# homeboard13.net
KiCad netlist of a schematic drawn in EAGLE
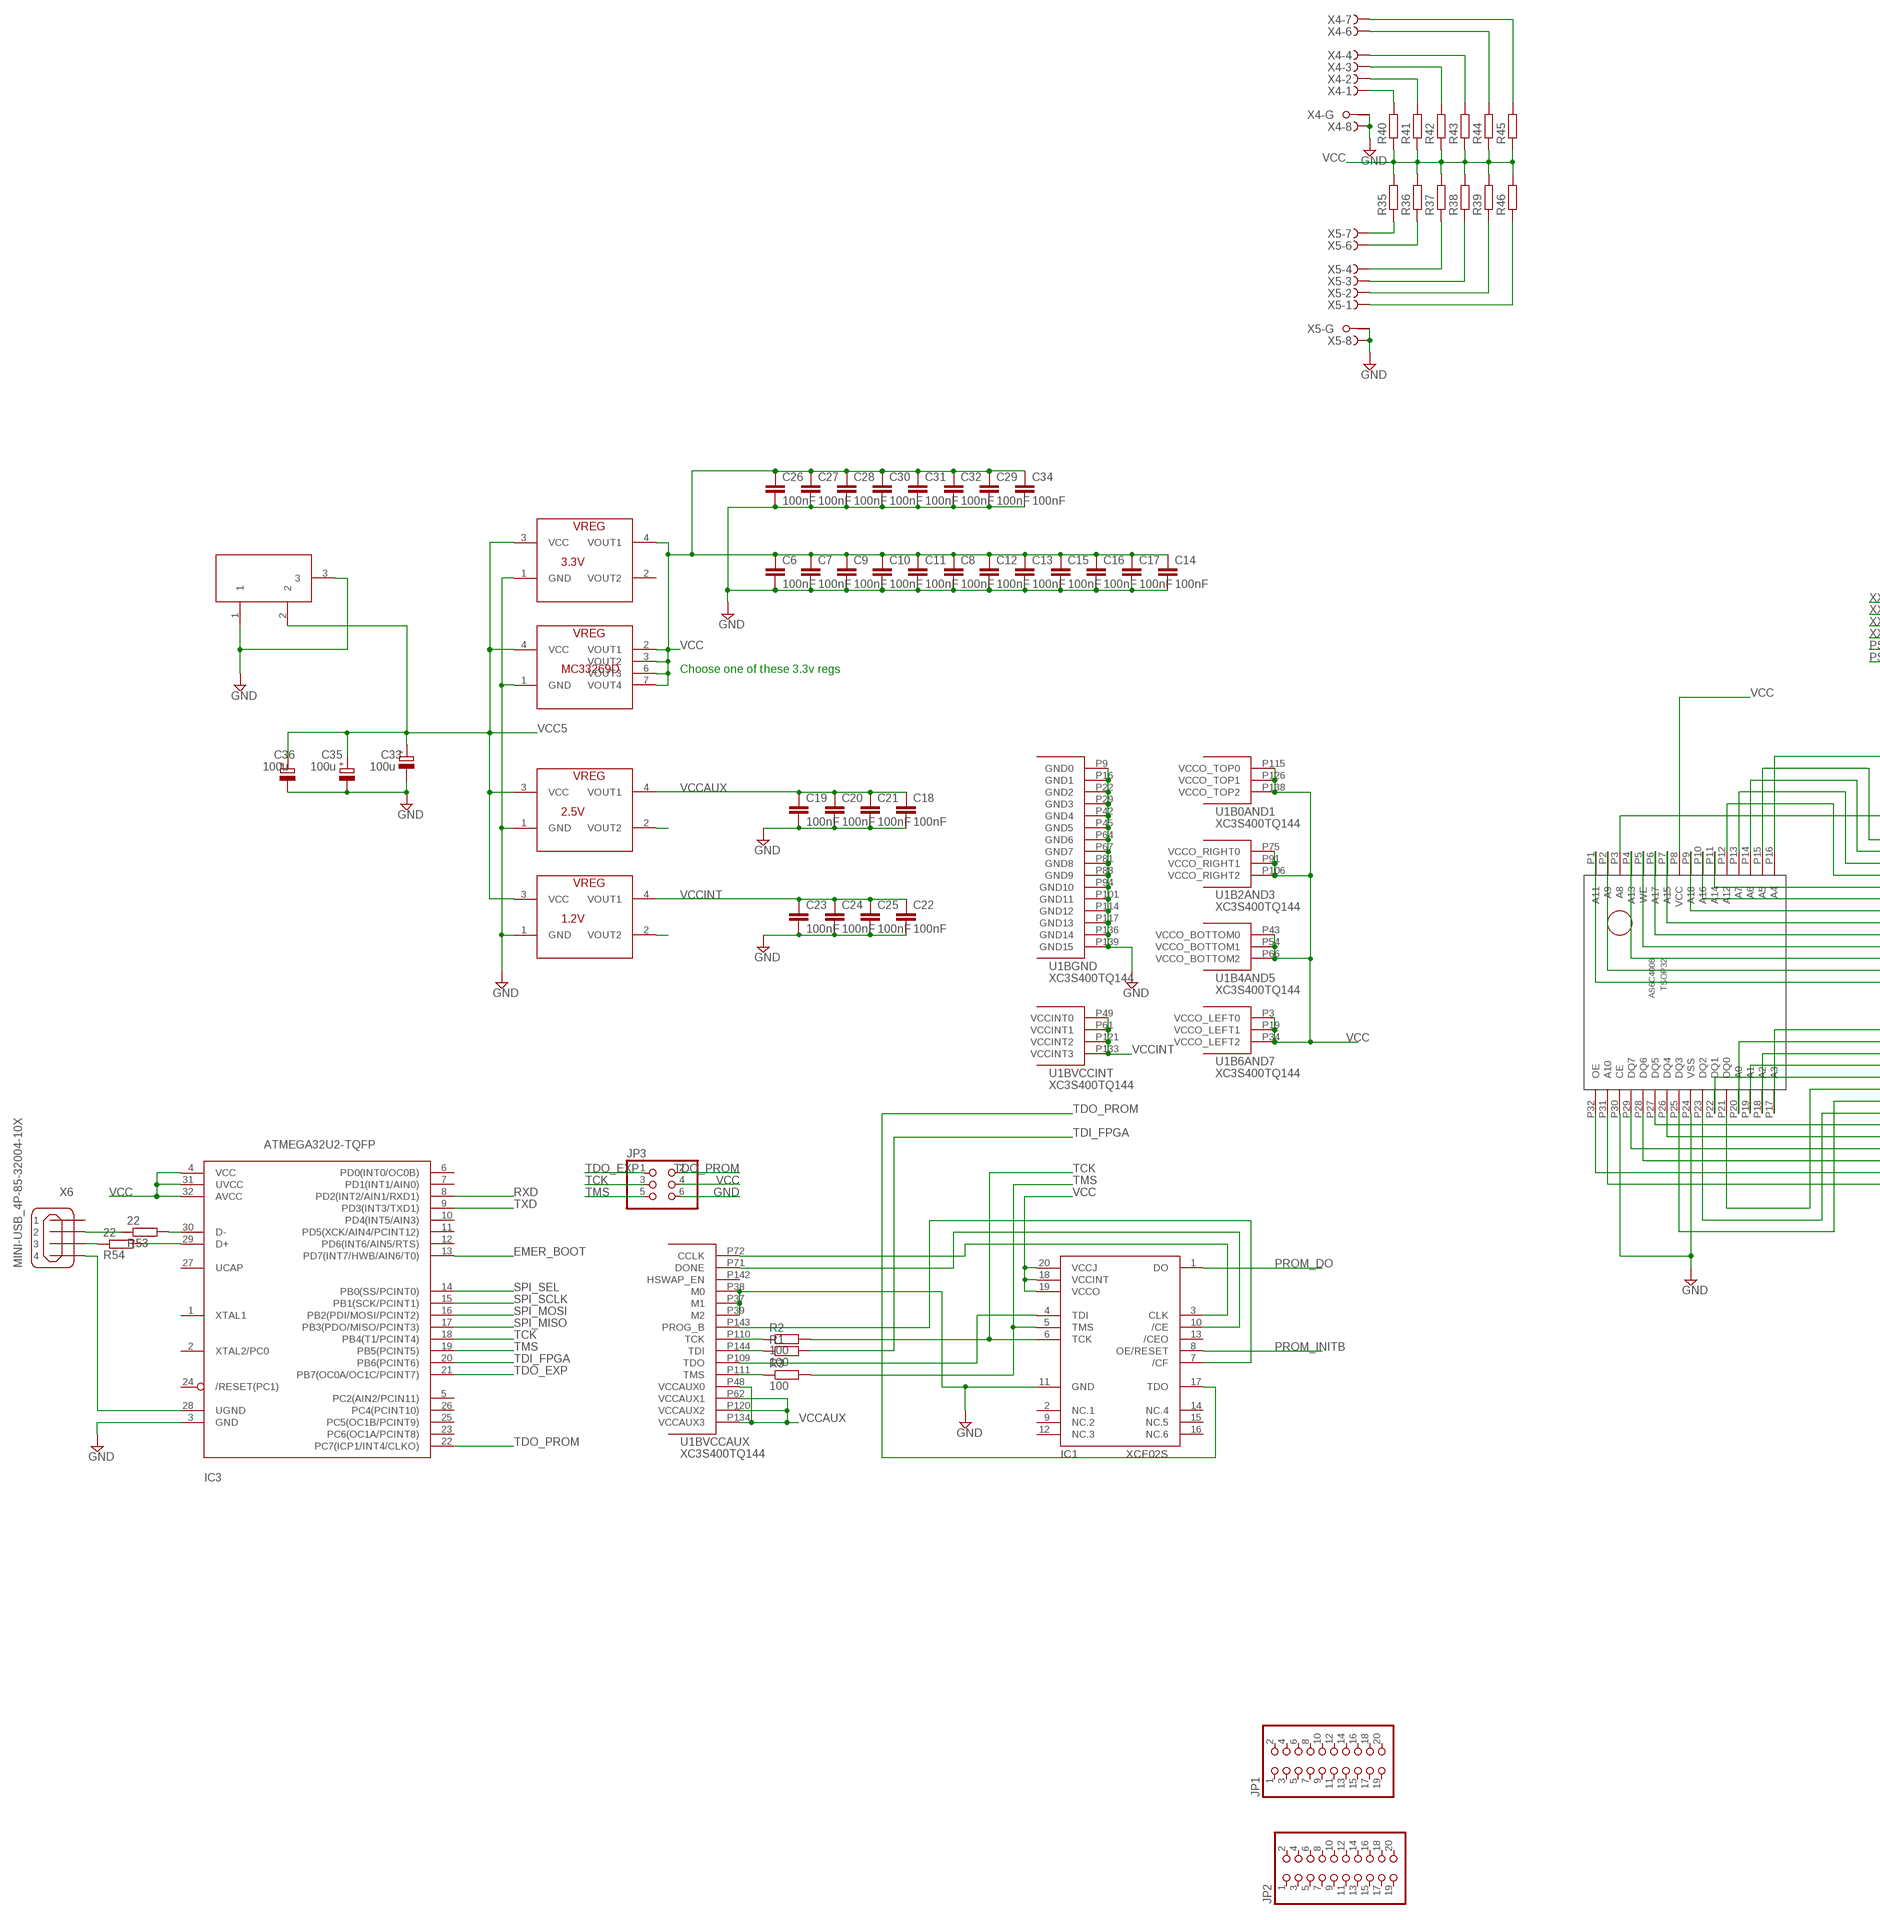
[diagram p0: schematic, sheet 1, part 1 of 3]
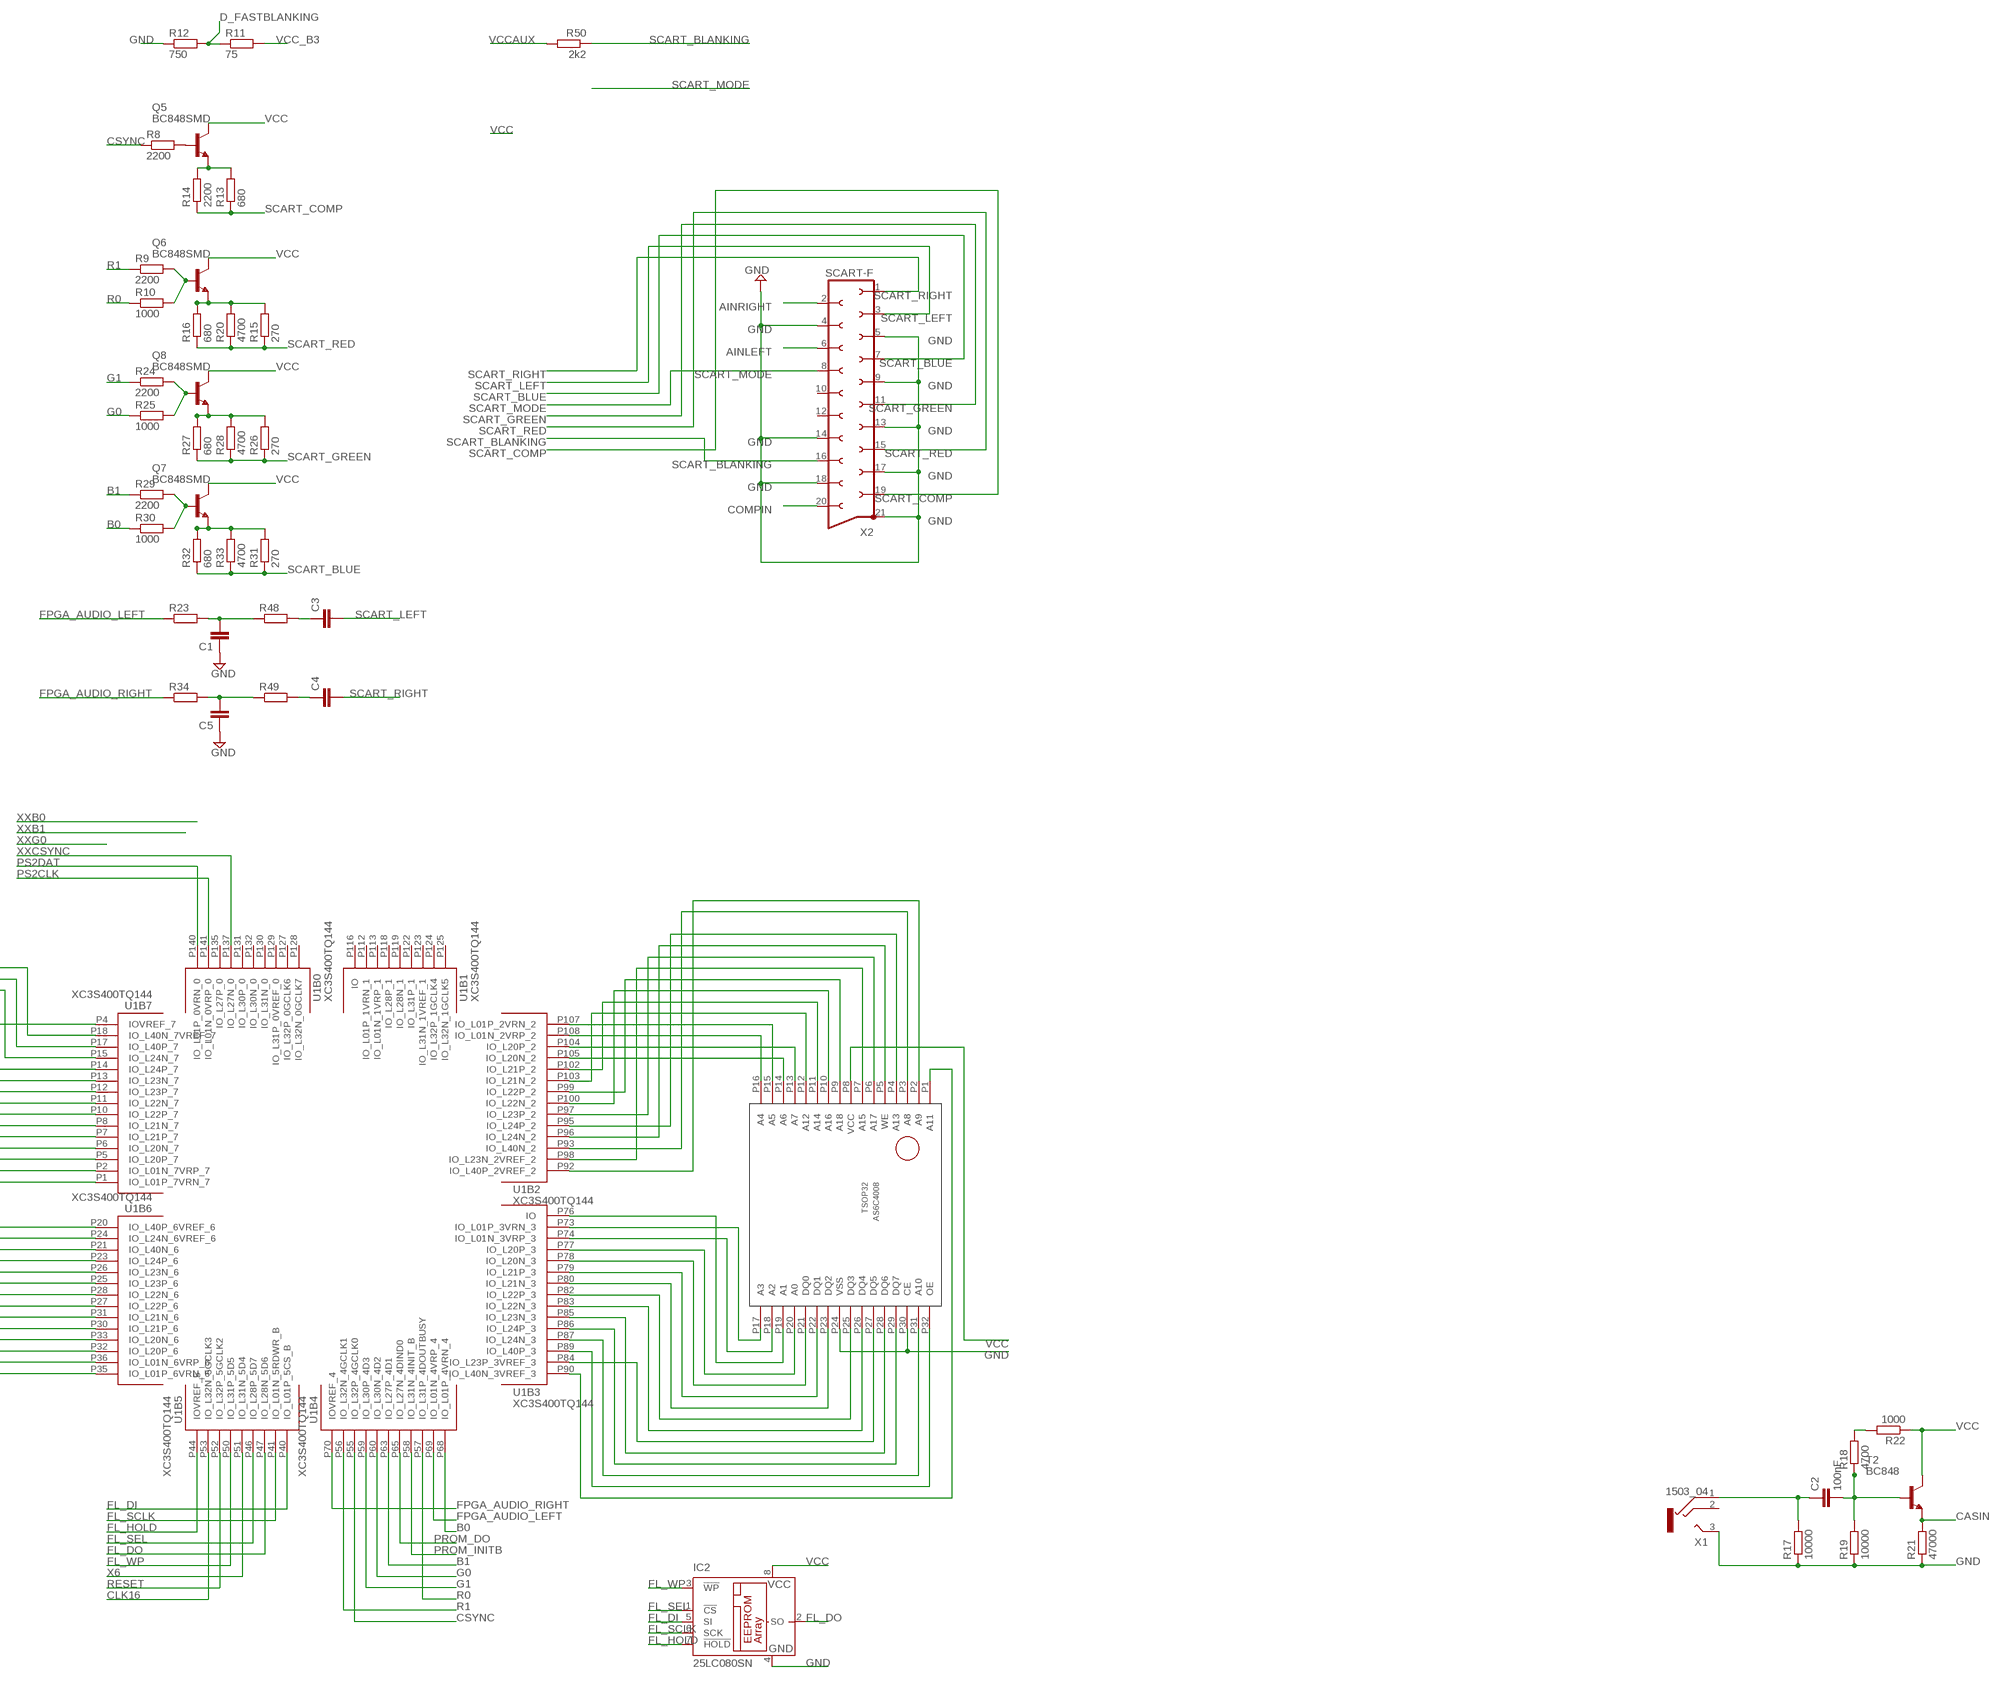
[diagram p1: schematic, sheet 1, part 2 of 3]
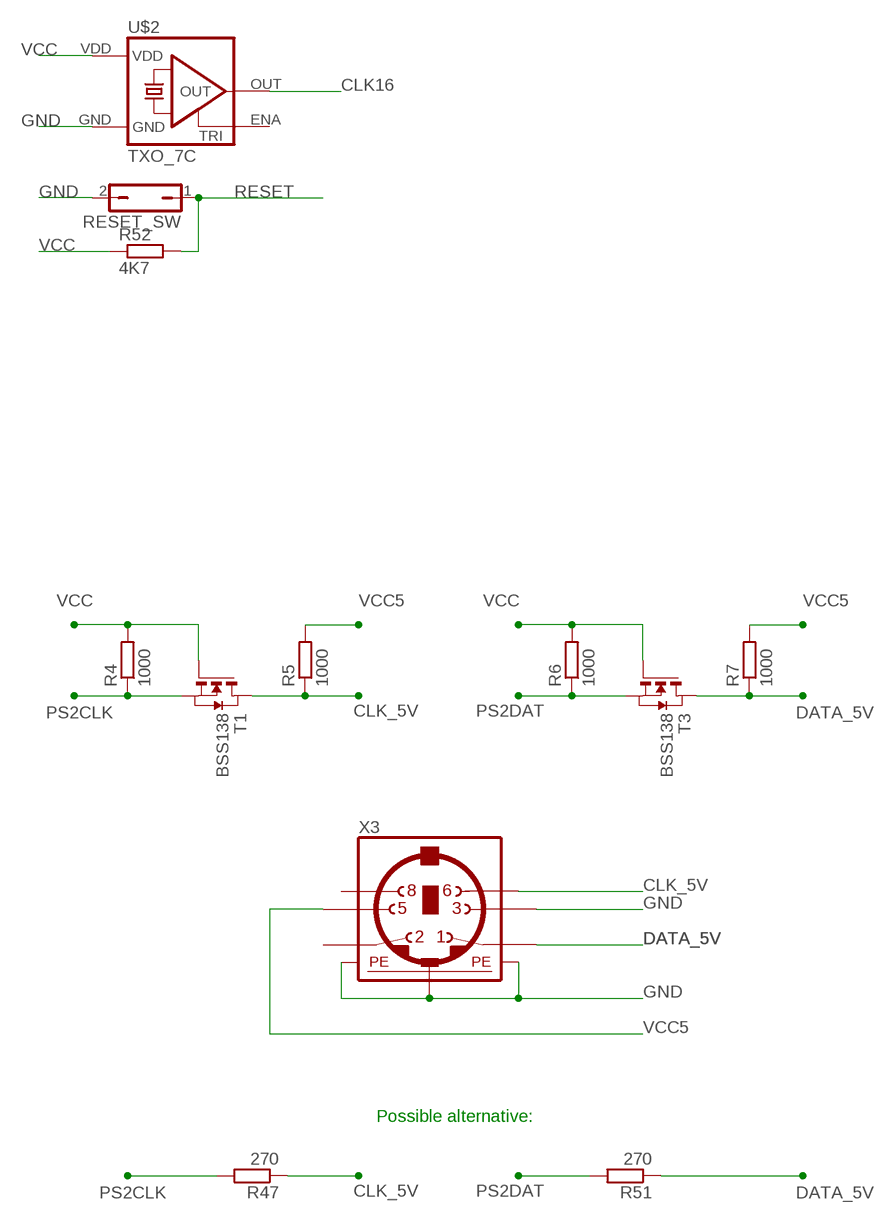
[diagram p2: schematic, sheet 1, part 3 of 3]

(export (version "E")
  (design (tool "Eeschema 10.0.6"))
  (components
    (comp (ref "C1")
      (value "C-EUC0603")
      (footprint "eagle-import:C0603")
      (libsource (lib "eagle-import") (part "resistor_C-EUC0603"))
    )
    (comp (ref "C2")
      (value "100nF")
      (footprint "eagle-import:C0603")
      (libsource (lib "eagle-import") (part "resistor_C-EUC0603"))
    )
    (comp (ref "C3")
      (value "C-EUC0603")
      (footprint "eagle-import:C0603")
      (libsource (lib "eagle-import") (part "resistor_C-EUC0603"))
    )
    (comp (ref "C4")
      (value "C-EUC0603")
      (footprint "eagle-import:C0603")
      (libsource (lib "eagle-import") (part "resistor_C-EUC0603"))
    )
    (comp (ref "C5")
      (value "C-EUC0603")
      (footprint "eagle-import:C0603")
      (libsource (lib "eagle-import") (part "resistor_C-EUC0603"))
    )
    (comp (ref "C6")
      (value "100nF")
      (footprint "eagle-import:C0603")
      (libsource (lib "eagle-import") (part "C-EUC0603"))
    )
    (comp (ref "C7")
      (value "100nF")
      (footprint "eagle-import:C0603")
      (libsource (lib "eagle-import") (part "C-EUC0603"))
    )
    (comp (ref "C8")
      (value "100nF")
      (footprint "eagle-import:C0603")
      (libsource (lib "eagle-import") (part "C-EUC0603"))
    )
    (comp (ref "C9")
      (value "100nF")
      (footprint "eagle-import:C0603")
      (libsource (lib "eagle-import") (part "C-EUC0603"))
    )
    (comp (ref "C10")
      (value "100nF")
      (footprint "eagle-import:C0603")
      (libsource (lib "eagle-import") (part "C-EUC0603"))
    )
    (comp (ref "C11")
      (value "100nF")
      (footprint "eagle-import:C0603")
      (libsource (lib "eagle-import") (part "C-EUC0603"))
    )
    (comp (ref "C12")
      (value "100nF")
      (footprint "eagle-import:C0603")
      (libsource (lib "eagle-import") (part "C-EUC0603"))
    )
    (comp (ref "C13")
      (value "100nF")
      (footprint "eagle-import:C0603")
      (libsource (lib "eagle-import") (part "C-EUC0603"))
    )
    (comp (ref "C14")
      (value "100nF")
      (footprint "eagle-import:C0603")
      (libsource (lib "eagle-import") (part "C-EUC0603"))
    )
    (comp (ref "C15")
      (value "100nF")
      (footprint "eagle-import:C0603")
      (libsource (lib "eagle-import") (part "C-EUC0603"))
    )
    (comp (ref "C16")
      (value "100nF")
      (footprint "eagle-import:C0603")
      (libsource (lib "eagle-import") (part "C-EUC0603"))
    )
    (comp (ref "C17")
      (value "100nF")
      (footprint "eagle-import:C0603")
      (libsource (lib "eagle-import") (part "C-EUC0603"))
    )
    (comp (ref "C18")
      (value "100nF")
      (footprint "eagle-import:C0603")
      (libsource (lib "eagle-import") (part "C-EUC0603"))
    )
    (comp (ref "C19")
      (value "100nF")
      (footprint "eagle-import:C0603")
      (libsource (lib "eagle-import") (part "C-EUC0603"))
    )
    (comp (ref "C20")
      (value "100nF")
      (footprint "eagle-import:C0603")
      (libsource (lib "eagle-import") (part "C-EUC0603"))
    )
    (comp (ref "C21")
      (value "100nF")
      (footprint "eagle-import:C0603")
      (libsource (lib "eagle-import") (part "C-EUC0603"))
    )
    (comp (ref "C22")
      (value "100nF")
      (footprint "eagle-import:C0603")
      (libsource (lib "eagle-import") (part "C-EUC0603"))
    )
    (comp (ref "C23")
      (value "100nF")
      (footprint "eagle-import:C0603")
      (libsource (lib "eagle-import") (part "C-EUC0603"))
    )
    (comp (ref "C24")
      (value "100nF")
      (footprint "eagle-import:C0603")
      (libsource (lib "eagle-import") (part "C-EUC0603"))
    )
    (comp (ref "C25")
      (value "100nF")
      (footprint "eagle-import:C0603")
      (libsource (lib "eagle-import") (part "C-EUC0603"))
    )
    (comp (ref "C26")
      (value "100nF")
      (footprint "eagle-import:C0603")
      (libsource (lib "eagle-import") (part "C-EUC0603"))
    )
    (comp (ref "C27")
      (value "100nF")
      (footprint "eagle-import:C0603")
      (libsource (lib "eagle-import") (part "C-EUC0603"))
    )
    (comp (ref "C28")
      (value "100nF")
      (footprint "eagle-import:C0603")
      (libsource (lib "eagle-import") (part "C-EUC0603"))
    )
    (comp (ref "C29")
      (value "100nF")
      (footprint "eagle-import:C0603")
      (libsource (lib "eagle-import") (part "C-EUC0603"))
    )
    (comp (ref "C30")
      (value "100nF")
      (footprint "eagle-import:C0603")
      (libsource (lib "eagle-import") (part "C-EUC0603"))
    )
    (comp (ref "C31")
      (value "100nF")
      (footprint "eagle-import:C0603")
      (libsource (lib "eagle-import") (part "C-EUC0603"))
    )
    (comp (ref "C32")
      (value "100nF")
      (footprint "eagle-import:C0603")
      (libsource (lib "eagle-import") (part "C-EUC0603"))
    )
    (comp (ref "C33")
      (value "100u")
      (footprint "eagle-import:PANASONIC_D")
      (libsource (lib "eagle-import") (part "CPOL-EUD"))
    )
    (comp (ref "C34")
      (value "100nF")
      (footprint "eagle-import:C0603")
      (libsource (lib "eagle-import") (part "C-EUC0603"))
    )
    (comp (ref "C35")
      (value "100u")
      (footprint "eagle-import:PANASONIC_D")
      (libsource (lib "eagle-import") (part "CPOL-EUD"))
    )
    (comp (ref "C36")
      (value "100u")
      (footprint "eagle-import:PANASONIC_D")
      (libsource (lib "eagle-import") (part "CPOL-EUD"))
    )
    (comp (ref "IC1")
      (value "XCF02S")
      (footprint "eagle-import:VO20")
      (libsource (lib "eagle-import") (part "XCF02S"))
    )
    (comp (ref "IC2")
      (value "25LC080SN")
      (footprint "eagle-import:SO-08")
      (fields (field (name "MF") "MICROCHIP") (field (name "MPN") "25LC080/SN"))
      (libsource (lib "eagle-import") (part "25SNLC080"))
    )
    (comp (ref "IC3")
      (value "ATMEGA32U2-TQFP")
      (footprint "eagle-import:TQFP32-08")
      (libsource (lib "eagle-import") (part "ATMEGA32U2-TQFP"))
    )
    (comp (ref "JP1")
      (value "PINHD-2X10")
      (footprint "eagle-import:2X10")
      (libsource (lib "eagle-import") (part "PINHD-2X10"))
    )
    (comp (ref "JP2")
      (value "PINHD-2X10")
      (footprint "eagle-import:2X10")
      (libsource (lib "eagle-import") (part "PINHD-2X10"))
    )
    (comp (ref "JP3")
      (value "PINHD-2X3")
      (footprint "eagle-import:2X03")
      (libsource (lib "eagle-import") (part "PINHD-2X3"))
    )
    (comp (ref "Q5")
      (value "BC848SMD")
      (footprint "eagle-import:SOT23")
      (libsource (lib "eagle-import") (part "BC848SMD"))
    )
    (comp (ref "Q6")
      (value "BC848SMD")
      (footprint "eagle-import:SOT23")
      (libsource (lib "eagle-import") (part "BC848SMD"))
    )
    (comp (ref "Q7")
      (value "BC848SMD")
      (footprint "eagle-import:SOT23")
      (libsource (lib "eagle-import") (part "BC848SMD"))
    )
    (comp (ref "Q8")
      (value "BC848SMD")
      (footprint "eagle-import:SOT23")
      (libsource (lib "eagle-import") (part "BC848SMD"))
    )
    (comp (ref "R1")
      (value "100")
      (footprint "eagle-import:R0805")
      (libsource (lib "eagle-import") (part "R-EU_R0805"))
    )
    (comp (ref "R2")
      (value "100")
      (footprint "eagle-import:R0805")
      (libsource (lib "eagle-import") (part "R-EU_R0805"))
    )
    (comp (ref "R3")
      (value "100")
      (footprint "eagle-import:R0805")
      (libsource (lib "eagle-import") (part "R-EU_R0805"))
    )
    (comp (ref "R4")
      (value "1000")
      (footprint "eagle-import:R0805")
      (libsource (lib "eagle-import") (part "R-EU_R0805"))
    )
    (comp (ref "R5")
      (value "1000")
      (footprint "eagle-import:R0805")
      (libsource (lib "eagle-import") (part "R-EU_R0805"))
    )
    (comp (ref "R6")
      (value "1000")
      (footprint "eagle-import:R0805")
      (libsource (lib "eagle-import") (part "R-EU_R0805"))
    )
    (comp (ref "R7")
      (value "1000")
      (footprint "eagle-import:R0805")
      (libsource (lib "eagle-import") (part "R-EU_R0805"))
    )
    (comp (ref "R8")
      (value "2200")
      (footprint "eagle-import:R0805")
      (libsource (lib "eagle-import") (part "R-EU_R0805"))
    )
    (comp (ref "R9")
      (value "2200")
      (footprint "eagle-import:R0805")
      (libsource (lib "eagle-import") (part "R-EU_R0805"))
    )
    (comp (ref "R10")
      (value "1000")
      (footprint "eagle-import:R0805")
      (libsource (lib "eagle-import") (part "R-EU_R0805"))
    )
    (comp (ref "R11")
      (value "75")
      (footprint "eagle-import:R0805")
      (libsource (lib "eagle-import") (part "R-EU_R0805"))
    )
    (comp (ref "R12")
      (value "750")
      (footprint "eagle-import:R0805")
      (libsource (lib "eagle-import") (part "R-EU_R0805"))
    )
    (comp (ref "R13")
      (value "680")
      (footprint "eagle-import:R0805")
      (libsource (lib "eagle-import") (part "R-EU_R0805"))
    )
    (comp (ref "R14")
      (value "2200")
      (footprint "eagle-import:R0805")
      (libsource (lib "eagle-import") (part "R-EU_R0805"))
    )
    (comp (ref "R15")
      (value "270")
      (footprint "eagle-import:R0805")
      (libsource (lib "eagle-import") (part "R-EU_R0805"))
    )
    (comp (ref "R16")
      (value "680")
      (footprint "eagle-import:R0805")
      (libsource (lib "eagle-import") (part "R-EU_R0805"))
    )
    (comp (ref "R17")
      (value "10000")
      (footprint "eagle-import:R0805")
      (libsource (lib "eagle-import") (part "R-EU_R0805"))
    )
    (comp (ref "R18")
      (value "4700")
      (footprint "eagle-import:R0805")
      (libsource (lib "eagle-import") (part "R-EU_R0805"))
    )
    (comp (ref "R19")
      (value "10000")
      (footprint "eagle-import:R0805")
      (libsource (lib "eagle-import") (part "R-EU_R0805"))
    )
    (comp (ref "R20")
      (value "4700")
      (footprint "eagle-import:R0805")
      (libsource (lib "eagle-import") (part "R-EU_R0805"))
    )
    (comp (ref "R21")
      (value "47000")
      (footprint "eagle-import:R0805")
      (libsource (lib "eagle-import") (part "R-EU_R0805"))
    )
    (comp (ref "R22")
      (value "1000")
      (footprint "eagle-import:R0805")
      (libsource (lib "eagle-import") (part "R-EU_R0805"))
    )
    (comp (ref "R23")
      (value "R-EU_M0805")
      (footprint "eagle-import:M0805")
      (libsource (lib "eagle-import") (part "resistor_R-EU_M0805"))
    )
    (comp (ref "R24")
      (value "2200")
      (footprint "eagle-import:R0805")
      (libsource (lib "eagle-import") (part "R-EU_R0805"))
    )
    (comp (ref "R25")
      (value "1000")
      (footprint "eagle-import:R0805")
      (libsource (lib "eagle-import") (part "R-EU_R0805"))
    )
    (comp (ref "R26")
      (value "270")
      (footprint "eagle-import:R0805")
      (libsource (lib "eagle-import") (part "R-EU_R0805"))
    )
    (comp (ref "R27")
      (value "680")
      (footprint "eagle-import:R0805")
      (libsource (lib "eagle-import") (part "R-EU_R0805"))
    )
    (comp (ref "R28")
      (value "4700")
      (footprint "eagle-import:R0805")
      (libsource (lib "eagle-import") (part "R-EU_R0805"))
    )
    (comp (ref "R29")
      (value "2200")
      (footprint "eagle-import:R0805")
      (libsource (lib "eagle-import") (part "R-EU_R0805"))
    )
    (comp (ref "R30")
      (value "1000")
      (footprint "eagle-import:R0805")
      (libsource (lib "eagle-import") (part "R-EU_R0805"))
    )
    (comp (ref "R31")
      (value "270")
      (footprint "eagle-import:R0805")
      (libsource (lib "eagle-import") (part "R-EU_R0805"))
    )
    (comp (ref "R32")
      (value "680")
      (footprint "eagle-import:R0805")
      (libsource (lib "eagle-import") (part "R-EU_R0805"))
    )
    (comp (ref "R33")
      (value "4700")
      (footprint "eagle-import:R0805")
      (libsource (lib "eagle-import") (part "R-EU_R0805"))
    )
    (comp (ref "R34")
      (value "R-EU_M0805")
      (footprint "eagle-import:M0805")
      (libsource (lib "eagle-import") (part "resistor_R-EU_M0805"))
    )
    (comp (ref "R35")
      (value "R-EU_M0805")
      (footprint "eagle-import:M0805")
      (libsource (lib "eagle-import") (part "resistor_R-EU_M0805"))
    )
    (comp (ref "R36")
      (value "R-EU_M0805")
      (footprint "eagle-import:M0805")
      (libsource (lib "eagle-import") (part "resistor_R-EU_M0805"))
    )
    (comp (ref "R37")
      (value "R-EU_M0805")
      (footprint "eagle-import:M0805")
      (libsource (lib "eagle-import") (part "resistor_R-EU_M0805"))
    )
    (comp (ref "R38")
      (value "R-EU_M0805")
      (footprint "eagle-import:M0805")
      (libsource (lib "eagle-import") (part "resistor_R-EU_M0805"))
    )
    (comp (ref "R39")
      (value "R-EU_M0805")
      (footprint "eagle-import:M0805")
      (libsource (lib "eagle-import") (part "resistor_R-EU_M0805"))
    )
    (comp (ref "R40")
      (value "R-EU_M0805")
      (footprint "eagle-import:M0805")
      (libsource (lib "eagle-import") (part "resistor_R-EU_M0805"))
    )
    (comp (ref "R41")
      (value "R-EU_M0805")
      (footprint "eagle-import:M0805")
      (libsource (lib "eagle-import") (part "resistor_R-EU_M0805"))
    )
    (comp (ref "R42")
      (value "R-EU_M0805")
      (footprint "eagle-import:M0805")
      (libsource (lib "eagle-import") (part "resistor_R-EU_M0805"))
    )
    (comp (ref "R43")
      (value "R-EU_M0805")
      (footprint "eagle-import:M0805")
      (libsource (lib "eagle-import") (part "resistor_R-EU_M0805"))
    )
    (comp (ref "R44")
      (value "R-EU_M0805")
      (footprint "eagle-import:M0805")
      (libsource (lib "eagle-import") (part "resistor_R-EU_M0805"))
    )
    (comp (ref "R45")
      (value "R-EU_M0805")
      (footprint "eagle-import:M0805")
      (libsource (lib "eagle-import") (part "resistor_R-EU_M0805"))
    )
    (comp (ref "R46")
      (value "R-EU_M0805")
      (footprint "eagle-import:M0805")
      (libsource (lib "eagle-import") (part "resistor_R-EU_M0805"))
    )
    (comp (ref "R47")
      (value "270")
      (footprint "eagle-import:R0805")
      (libsource (lib "eagle-import") (part "R-EU_R0805"))
    )
    (comp (ref "R48")
      (value "R-EU_M0805")
      (footprint "eagle-import:M0805")
      (libsource (lib "eagle-import") (part "resistor_R-EU_M0805"))
    )
    (comp (ref "R49")
      (value "R-EU_M0805")
      (footprint "eagle-import:M0805")
      (libsource (lib "eagle-import") (part "resistor_R-EU_M0805"))
    )
    (comp (ref "R50")
      (value "2k2")
      (footprint "eagle-import:M0805")
      (libsource (lib "eagle-import") (part "resistor_R-EU_M0805"))
    )
    (comp (ref "R51")
      (value "270")
      (footprint "eagle-import:R0805")
      (libsource (lib "eagle-import") (part "R-EU_R0805"))
    )
    (comp (ref "R52")
      (value "4K7")
      (footprint "eagle-import:M0805")
      (libsource (lib "eagle-import") (part "resistor_R-EU_M0805"))
    )
    (comp (ref "R53")
      (value "22")
      (footprint "eagle-import:R0805")
      (libsource (lib "eagle-import") (part "R-EU_R0805"))
    )
    (comp (ref "R54")
      (value "22")
      (footprint "eagle-import:R0805")
      (libsource (lib "eagle-import") (part "R-EU_R0805"))
    )
    (comp (ref "REG1.2")
      (value "1.2V")
      (footprint "eagle-import:SOT223")
      (libsource (lib "eagle-import") (part "NX1117"))
    )
    (comp (ref "REG2.5")
      (value "2.5V")
      (footprint "eagle-import:SOT223")
      (libsource (lib "eagle-import") (part "NX1117"))
    )
    (comp (ref "RESET_SW")
      (value "JP1Q")
      (footprint "eagle-import:JP1")
      (libsource (lib "eagle-import") (part "JP1Q"))
    )
    (comp (ref "T1")
      (value "BSS138")
      (footprint "eagle-import:SOT-23")
      (libsource (lib "eagle-import") (part "NMOSSOT23"))
    )
    (comp (ref "T2")
      (value "BC848")
      (footprint "eagle-import:SOT23")
      (libsource (lib "eagle-import") (part "BC848"))
    )
    (comp (ref "T3")
      (value "BSS138")
      (footprint "eagle-import:SOT-23")
      (libsource (lib "eagle-import") (part "NMOSSOT23"))
    )
    (comp (ref "U$1")
      (value "AS6C4008")
      (footprint "eagle-import:TSOP32")
      (libsource (lib "eagle-import") (part "AS6C4008"))
    )
    (comp (ref "U$2")
      (value "TXO_7C")
      (footprint "eagle-import:OSC_7C")
      (libsource (lib "eagle-import") (part "TXO_7C"))
    )
    (comp (ref "U$4")
      (value "3.3V")
      (footprint "eagle-import:SOT223")
      (libsource (lib "eagle-import") (part "NX1117"))
    )
    (comp (ref "U$5")
      (value "MC33269D")
      (footprint "eagle-import:SO8")
      (libsource (lib "eagle-import") (part "MC33269D"))
    )
    (comp (ref "U$6")
      (value "AS6C4008")
      (footprint "eagle-import:TSOP32")
      (libsource (lib "eagle-import") (part "AS6C4008"))
    )
    (comp (ref "U1")
      (value "XC3S400TQ144")
      (footprint "eagle-import:TQ144")
      (libsource (lib "eagle-import") (part "XC3S400TQ144"))
    )
    (comp (ref "X1")
      (value "1503_04")
      (footprint "eagle-import:1503_04")
      (libsource (lib "eagle-import") (part "1503_04"))
    )
    (comp (ref "X2")
      (value "SCART-F")
      (footprint "eagle-import:SCART-F")
      (libsource (lib "eagle-import") (part "SCART-F"))
    )
    (comp (ref "X3")
      (value "MINI_DIN_6")
      (footprint "eagle-import:M_DIN6")
      (libsource (lib "eagle-import") (part "MINI_DIN_6"))
    )
    (comp (ref "X4")
      (value "F09HPS")
      (footprint "eagle-import:F09HP")
      (libsource (lib "eagle-import") (part "F09HPS"))
    )
    (comp (ref "X5")
      (value "F09HPS")
      (footprint "eagle-import:F09HP")
      (libsource (lib "eagle-import") (part "F09HPS"))
    )
    (comp (ref "X6")
      (value "MINI-USB_4P-85-32004-10X")
      (footprint "eagle-import:85-32004-10X")
      (libsource (lib "eagle-import") (part "MINI-USB_4P-85-32004-10X"))
    )
    (comp (ref "X8")
      (value "DC21MMX")
      (footprint "eagle-import:DC-21MM")
      (libsource (lib "eagle-import") (part "DC21MMX"))
    )
  )
  (nets
    (net (code "1") (name "/AINLEFT") (class "Default")
      (node (ref "X2") (pin "6") (pinfunction "6_6") (pintype "passive"))
    )
    (net (code "2") (name "/AINRIGHT") (class "Default")
      (node (ref "X2") (pin "2") (pinfunction "2_2") (pintype "passive"))
    )
    (net (code "3") (name "/B0") (class "Default")
      (node (ref "R30") (pin "1") (pinfunction "1_1") (pintype "passive"))
      (node (ref "U1") (pin "P68") (pinfunction "IO_L01P_4VRN_4_P68") (pintype "bidirectional"))
    )
    (net (code "4") (name "/B1") (class "Default")
      (node (ref "R29") (pin "1") (pinfunction "1_1") (pintype "passive"))
      (node (ref "U1") (pin "P63") (pinfunction "IO_L27P_4D1_P63") (pintype "bidirectional"))
    )
    (net (code "5") (name "/CASIN") (class "Default")
      (node (ref "R21") (pin "2") (pinfunction "2_2") (pintype "passive"))
      (node (ref "T2") (pin "2") (pinfunction "E_2") (pintype "passive"))
    )
    (net (code "6") (name "/CLK16") (class "Default")
      (node (ref "U$2") (pin "OUT") (pinfunction "OUT_OUT") (pintype "output"))
      (node (ref "U1") (pin "P53") (pinfunction "IO_L32N_5GCLK3_P53") (pintype "bidirectional"))
    )
    (net (code "7") (name "/CLK_5V") (class "Default")
      (node (ref "R47") (pin "1") (pinfunction "1_1") (pintype "passive"))
      (node (ref "R5") (pin "1") (pinfunction "1_1") (pintype "passive"))
      (node (ref "T1") (pin "1") (pinfunction "D_1") (pintype "passive"))
      (node (ref "X3") (pin "6") (pinfunction "6_6") (pintype "passive"))
    )
    (net (code "8") (name "/COMPIN") (class "Default")
      (node (ref "X2") (pin "20") (pinfunction "20_20") (pintype "passive"))
    )
    (net (code "9") (name "/CSYNC") (class "Default")
      (node (ref "R8") (pin "1") (pinfunction "1_1") (pintype "passive"))
      (node (ref "U1") (pin "P55") (pinfunction "IO_L32P_4GCLK0_P55") (pintype "bidirectional"))
    )
    (net (code "10") (name "/DATA_5V") (class "Default")
      (node (ref "R51") (pin "1") (pinfunction "1_1") (pintype "passive"))
      (node (ref "R7") (pin "1") (pinfunction "1_1") (pintype "passive"))
      (node (ref "T3") (pin "1") (pinfunction "D_1") (pintype "passive"))
      (node (ref "X3") (pin "1") (pinfunction "1_1") (pintype "passive"))
    )
    (net (code "11") (name "/D_FASTBLANKING") (class "Default")
      (node (ref "R11") (pin "1") (pinfunction "1_1") (pintype "passive"))
      (node (ref "R12") (pin "2") (pinfunction "2_2") (pintype "passive"))
    )
    (net (code "12") (name "/EMER_BOOT") (class "Default")
      (node (ref "IC3") (pin "13") (pinfunction "PD7(INT7/HWB/AIN6/T0)_13") (pintype "bidirectional"))
    )
    (net (code "13") (name "/FL_DI") (class "Default")
      (node (ref "IC2") (pin "5") (pinfunction "SI_5") (pintype "input"))
      (node (ref "U1") (pin "P40") (pinfunction "IO_L01P_5CS_B_P40") (pintype "bidirectional"))
    )
    (net (code "14") (name "/FL_DO") (class "Default")
      (node (ref "IC2") (pin "2") (pinfunction "SO_2") (pintype "bidirectional"))
      (node (ref "U1") (pin "P47") (pinfunction "IO_L28N_5D6_P47") (pintype "bidirectional"))
    )
    (net (code "15") (name "/FL_HOLD") (class "Default")
      (node (ref "IC2") (pin "7") (pinfunction "~{HOLD}_7") (pintype "input"))
      (node (ref "U1") (pin "P44") (pinfunction "IOVREF_5_P44") (pintype "bidirectional"))
    )
    (net (code "16") (name "/FL_SCLK") (class "Default")
      (node (ref "IC2") (pin "6") (pinfunction "SCK_6") (pintype "input"))
      (node (ref "U1") (pin "P41") (pinfunction "IO_L01N_5RDWR_B_P41") (pintype "bidirectional"))
    )
    (net (code "17") (name "/FL_SEL") (class "Default")
      (node (ref "IC2") (pin "1") (pinfunction "~{CS}_1") (pintype "input"))
      (node (ref "U1") (pin "P46") (pinfunction "IO_L28P_5D7_P46") (pintype "bidirectional"))
    )
    (net (code "18") (name "/FL_WP") (class "Default")
      (node (ref "IC2") (pin "3") (pinfunction "~{WP}_3") (pintype "input"))
      (node (ref "U1") (pin "P50") (pinfunction "IO_L31P_5D5_P50") (pintype "bidirectional"))
    )
    (net (code "19") (name "/FPGA_AUDIO_LEFT") (class "Default")
      (node (ref "R23") (pin "1") (pinfunction "1_1") (pintype "passive"))
      (node (ref "U1") (pin "P69") (pinfunction "IO_L01N_4VRP_4_P69") (pintype "bidirectional"))
    )
    (net (code "20") (name "/FPGA_AUDIO_RIGHT") (class "Default")
      (node (ref "R34") (pin "1") (pinfunction "1_1") (pintype "passive"))
      (node (ref "U1") (pin "P70") (pinfunction "IOVREF_4_P70") (pintype "bidirectional"))
    )
    (net (code "21") (name "/G0") (class "Default")
      (node (ref "R25") (pin "1") (pinfunction "1_1") (pintype "passive"))
      (node (ref "U1") (pin "P60") (pinfunction "IO_L30N_4D2_P60") (pintype "bidirectional"))
    )
    (net (code "22") (name "/G1") (class "Default")
      (node (ref "R24") (pin "1") (pinfunction "1_1") (pintype "passive"))
      (node (ref "U1") (pin "P59") (pinfunction "IO_L30P_4D3_P59") (pintype "bidirectional"))
    )
    (net (code "23") (name "/PROM_DO") (class "Default")
      (node (ref "IC1") (pin "1") (pinfunction "DO_1") (pintype "bidirectional"))
      (node (ref "U1") (pin "P65") (pinfunction "IO_L27N_4DIND0_P65") (pintype "bidirectional"))
    )
    (net (code "24") (name "/PROM_INITB") (class "Default")
      (node (ref "IC1") (pin "8") (pinfunction "OE/RESET_8") (pintype "bidirectional"))
      (node (ref "U1") (pin "P58") (pinfunction "IO_L31N_4INIT_B_P58") (pintype "bidirectional"))
    )
    (net (code "25") (name "/PS2CLK") (class "Default")
      (node (ref "R4") (pin "1") (pinfunction "1_1") (pintype "passive"))
      (node (ref "R47") (pin "2") (pinfunction "2_2") (pintype "passive"))
      (node (ref "T1") (pin "2") (pinfunction "S_2") (pintype "passive"))
      (node (ref "U1") (pin "P141") (pinfunction "IO_L01N_0VRP_0_P141") (pintype "bidirectional"))
    )
    (net (code "26") (name "/PS2DAT") (class "Default")
      (node (ref "R51") (pin "2") (pinfunction "2_2") (pintype "passive"))
      (node (ref "R6") (pin "1") (pinfunction "1_1") (pintype "passive"))
      (node (ref "T3") (pin "2") (pinfunction "S_2") (pintype "passive"))
      (node (ref "U1") (pin "P140") (pinfunction "IO_L01P_0VRN_0_P140") (pintype "bidirectional"))
    )
    (net (code "27") (name "/R0") (class "Default")
      (node (ref "R10") (pin "1") (pinfunction "1_1") (pintype "passive"))
      (node (ref "U1") (pin "P57") (pinfunction "IO_L31P_4DOUTBUSY_P57") (pintype "bidirectional"))
    )
    (net (code "28") (name "/R1") (class "Default")
      (node (ref "R9") (pin "1") (pinfunction "1_1") (pintype "passive"))
      (node (ref "U1") (pin "P56") (pinfunction "IO_L32N_4GCLK1_P56") (pintype "bidirectional"))
    )
    (net (code "29") (name "/RESET") (class "Default")
      (node (ref "R52") (pin "2") (pinfunction "2_2") (pintype "passive"))
      (node (ref "RESET_SW") (pin "1") (pinfunction "1_1") (pintype "passive"))
      (node (ref "U1") (pin "P52") (pinfunction "IO_L32P_5GCLK2_P52") (pintype "bidirectional"))
    )
    (net (code "30") (name "/RXD") (class "Default")
      (node (ref "IC3") (pin "8") (pinfunction "PD2(INT2/AIN1/RXD1)_8") (pintype "bidirectional"))
    )
    (net (code "31") (name "/SCART_BLANKING") (class "Default")
      (node (ref "R50") (pin "1") (pinfunction "1_1") (pintype "passive"))
      (node (ref "X2") (pin "16") (pinfunction "16_16") (pintype "passive"))
    )
    (net (code "32") (name "/SCART_BLUE") (class "Default")
      (node (ref "R31") (pin "1") (pinfunction "1_1") (pintype "passive"))
      (node (ref "R32") (pin "1") (pinfunction "1_1") (pintype "passive"))
      (node (ref "R33") (pin "1") (pinfunction "1_1") (pintype "passive"))
      (node (ref "X2") (pin "7") (pinfunction "7_7") (pintype "passive"))
    )
    (net (code "33") (name "/SCART_COMP") (class "Default")
      (node (ref "R13") (pin "1") (pinfunction "1_1") (pintype "passive"))
      (node (ref "R14") (pin "1") (pinfunction "1_1") (pintype "passive"))
      (node (ref "X2") (pin "19") (pinfunction "19_19") (pintype "passive"))
    )
    (net (code "34") (name "/SCART_GREEN") (class "Default")
      (node (ref "R26") (pin "1") (pinfunction "1_1") (pintype "passive"))
      (node (ref "R27") (pin "1") (pinfunction "1_1") (pintype "passive"))
      (node (ref "R28") (pin "1") (pinfunction "1_1") (pintype "passive"))
      (node (ref "X2") (pin "11") (pinfunction "11_11") (pintype "passive"))
    )
    (net (code "35") (name "/SCART_LEFT") (class "Default")
      (node (ref "C3") (pin "2") (pinfunction "2_2") (pintype "passive"))
      (node (ref "X2") (pin "3") (pinfunction "3_3") (pintype "passive"))
    )
    (net (code "36") (name "/SCART_MODE") (class "Default")
      (node (ref "X2") (pin "8") (pinfunction "8_8") (pintype "passive"))
    )
    (net (code "37") (name "/SCART_RED") (class "Default")
      (node (ref "R15") (pin "1") (pinfunction "1_1") (pintype "passive"))
      (node (ref "R16") (pin "1") (pinfunction "1_1") (pintype "passive"))
      (node (ref "R20") (pin "1") (pinfunction "1_1") (pintype "passive"))
      (node (ref "X2") (pin "15") (pinfunction "15_15") (pintype "passive"))
    )
    (net (code "38") (name "/SCART_RIGHT") (class "Default")
      (node (ref "C4") (pin "2") (pinfunction "2_2") (pintype "passive"))
      (node (ref "X2") (pin "1") (pinfunction "1_1") (pintype "passive"))
    )
    (net (code "39") (name "/SPI_MISO") (class "Default")
      (node (ref "IC3") (pin "17") (pinfunction "PB3(PDO/MISO/PCINT3)_17") (pintype "bidirectional"))
    )
    (net (code "40") (name "/SPI_MOSI") (class "Default")
      (node (ref "IC3") (pin "16") (pinfunction "PB2(PDI/MOSI/PCINT2)_16") (pintype "bidirectional"))
    )
    (net (code "41") (name "/SPI_SCLK") (class "Default")
      (node (ref "IC3") (pin "15") (pinfunction "PB1(SCK/PCINT1)_15") (pintype "bidirectional"))
    )
    (net (code "42") (name "/SPI_SEL") (class "Default")
      (node (ref "IC3") (pin "14") (pinfunction "PB0(SS/PCINT0)_14") (pintype "bidirectional"))
    )
    (net (code "43") (name "/TCK") (class "Default")
      (node (ref "IC1") (pin "6") (pinfunction "TCK_6") (pintype "bidirectional"))
      (node (ref "IC3") (pin "18") (pinfunction "PB4(T1/PCINT4)_18") (pintype "bidirectional"))
      (node (ref "JP3") (pin "3") (pinfunction "3_3") (pintype "passive"))
      (node (ref "R2") (pin "2") (pinfunction "2_2") (pintype "passive"))
    )
    (net (code "44") (name "/TDI_FPGA") (class "Default")
      (node (ref "IC3") (pin "20") (pinfunction "PB6(PCINT6)_20") (pintype "bidirectional"))
      (node (ref "R1") (pin "2") (pinfunction "2_2") (pintype "passive"))
    )
    (net (code "45") (name "/TDO_EXP") (class "Default")
      (node (ref "IC3") (pin "21") (pinfunction "PB7(OC0A/OC1C/PCINT7)_21") (pintype "bidirectional"))
      (node (ref "JP3") (pin "1") (pinfunction "1_1") (pintype "passive"))
    )
    (net (code "46") (name "/TDO_PROM") (class "Default")
      (node (ref "IC1") (pin "17") (pinfunction "TDO_17") (pintype "bidirectional"))
      (node (ref "IC3") (pin "22") (pinfunction "PC7(ICP1/INT4/CLKO)_22") (pintype "bidirectional"))
      (node (ref "JP3") (pin "2") (pinfunction "2_2") (pintype "passive"))
    )
    (net (code "47") (name "/TMS") (class "Default")
      (node (ref "IC1") (pin "5") (pinfunction "TMS_5") (pintype "bidirectional"))
      (node (ref "IC3") (pin "19") (pinfunction "PB5(PCINT5)_19") (pintype "bidirectional"))
      (node (ref "JP3") (pin "5") (pinfunction "5_5") (pintype "passive"))
      (node (ref "R3") (pin "2") (pinfunction "2_2") (pintype "passive"))
    )
    (net (code "48") (name "/TXD") (class "Default")
      (node (ref "IC3") (pin "9") (pinfunction "PD3(INT3/TXD1)_9") (pintype "bidirectional"))
    )
    (net (code "49") (name "/VCC") (class "Default")
      (node (ref "C10") (pin "1") (pinfunction "1_1") (pintype "passive"))
      (node (ref "C11") (pin "1") (pinfunction "1_1") (pintype "passive"))
      (node (ref "C12") (pin "1") (pinfunction "1_1") (pintype "passive"))
      (node (ref "C13") (pin "1") (pinfunction "1_1") (pintype "passive"))
      (node (ref "C14") (pin "1") (pinfunction "1_1") (pintype "passive"))
      (node (ref "C15") (pin "1") (pinfunction "1_1") (pintype "passive"))
      (node (ref "C16") (pin "1") (pinfunction "1_1") (pintype "passive"))
      (node (ref "C17") (pin "1") (pinfunction "1_1") (pintype "passive"))
      (node (ref "C26") (pin "1") (pinfunction "1_1") (pintype "passive"))
      (node (ref "C27") (pin "1") (pinfunction "1_1") (pintype "passive"))
      (node (ref "C28") (pin "1") (pinfunction "1_1") (pintype "passive"))
      (node (ref "C29") (pin "1") (pinfunction "1_1") (pintype "passive"))
      (node (ref "C30") (pin "1") (pinfunction "1_1") (pintype "passive"))
      (node (ref "C31") (pin "1") (pinfunction "1_1") (pintype "passive"))
      (node (ref "C32") (pin "1") (pinfunction "1_1") (pintype "passive"))
      (node (ref "C34") (pin "1") (pinfunction "1_1") (pintype "passive"))
      (node (ref "C6") (pin "1") (pinfunction "1_1") (pintype "passive"))
      (node (ref "C7") (pin "1") (pinfunction "1_1") (pintype "passive"))
      (node (ref "C8") (pin "1") (pinfunction "1_1") (pintype "passive"))
      (node (ref "C9") (pin "1") (pinfunction "1_1") (pintype "passive"))
      (node (ref "IC1") (pin "18") (pinfunction "VCCINT_18") (pintype "bidirectional"))
      (node (ref "IC1") (pin "19") (pinfunction "VCCO_19") (pintype "bidirectional"))
      (node (ref "IC1") (pin "20") (pinfunction "VCCJ_20") (pintype "bidirectional"))
      (node (ref "IC2") (pin "8") (pinfunction "VCC_8") (pintype "power_in"))
      (node (ref "IC3") (pin "31") (pinfunction "UVCC_31") (pintype "bidirectional"))
      (node (ref "IC3") (pin "32") (pinfunction "AVCC_32") (pintype "bidirectional"))
      (node (ref "IC3") (pin "4") (pinfunction "VCC_4") (pintype "bidirectional"))
      (node (ref "JP3") (pin "4") (pinfunction "4_4") (pintype "passive"))
      (node (ref "Q5") (pin "3") (pinfunction "C_3") (pintype "passive"))
      (node (ref "Q6") (pin "3") (pinfunction "C_3") (pintype "passive"))
      (node (ref "Q7") (pin "3") (pinfunction "C_3") (pintype "passive"))
      (node (ref "Q8") (pin "3") (pinfunction "C_3") (pintype "passive"))
      (node (ref "R22") (pin "1") (pinfunction "1_1") (pintype "passive"))
      (node (ref "R35") (pin "2") (pinfunction "2_2") (pintype "passive"))
      (node (ref "R36") (pin "2") (pinfunction "2_2") (pintype "passive"))
      (node (ref "R37") (pin "2") (pinfunction "2_2") (pintype "passive"))
      (node (ref "R38") (pin "2") (pinfunction "2_2") (pintype "passive"))
      (node (ref "R39") (pin "2") (pinfunction "2_2") (pintype "passive"))
      (node (ref "R4") (pin "2") (pinfunction "2_2") (pintype "passive"))
      (node (ref "R40") (pin "1") (pinfunction "1_1") (pintype "passive"))
      (node (ref "R41") (pin "1") (pinfunction "1_1") (pintype "passive"))
      (node (ref "R42") (pin "1") (pinfunction "1_1") (pintype "passive"))
      (node (ref "R43") (pin "1") (pinfunction "1_1") (pintype "passive"))
      (node (ref "R44") (pin "1") (pinfunction "1_1") (pintype "passive"))
      (node (ref "R45") (pin "1") (pinfunction "1_1") (pintype "passive"))
      (node (ref "R46") (pin "2") (pinfunction "2_2") (pintype "passive"))
      (node (ref "R52") (pin "1") (pinfunction "1_1") (pintype "passive"))
      (node (ref "R6") (pin "2") (pinfunction "2_2") (pintype "passive"))
      (node (ref "T1") (pin "3") (pinfunction "G_3") (pintype "passive"))
      (node (ref "T2") (pin "3") (pinfunction "C_3") (pintype "passive"))
      (node (ref "T3") (pin "3") (pinfunction "G_3") (pintype "passive"))
      (node (ref "U$1") (pin "P8") (pinfunction "VCC_P8") (pintype "bidirectional"))
      (node (ref "U$2") (pin "VDD") (pinfunction "VDD_VDD") (pintype "power_in"))
      (node (ref "U$4") (pin "4") (pinfunction "VOUT1_4") (pintype "bidirectional"))
      (node (ref "U$5") (pin "2") (pinfunction "VOUT1_2") (pintype "output"))
      (node (ref "U$5") (pin "3") (pinfunction "VOUT2_3") (pintype "output"))
      (node (ref "U$5") (pin "6") (pinfunction "VOUT3_6") (pintype "output"))
      (node (ref "U$5") (pin "7") (pinfunction "VOUT4_7") (pintype "output"))
      (node (ref "U$6") (pin "P8") (pinfunction "VCC_P8") (pintype "bidirectional"))
      (node (ref "U1") (pin "P106") (pinfunction "VCCO_RIGHT2_P106") (pintype "passive"))
      (node (ref "U1") (pin "P115") (pinfunction "VCCO_TOP0_P115") (pintype "passive"))
      (node (ref "U1") (pin "P126") (pinfunction "VCCO_TOP1_P126") (pintype "passive"))
      (node (ref "U1") (pin "P138") (pinfunction "VCCO_TOP2_P138") (pintype "passive"))
      (node (ref "U1") (pin "P19") (pinfunction "VCCO_LEFT1_P19") (pintype "passive"))
      (node (ref "U1") (pin "P3") (pinfunction "VCCO_LEFT0_P3") (pintype "passive"))
      (node (ref "U1") (pin "P34") (pinfunction "VCCO_LEFT2_P34") (pintype "passive"))
      (node (ref "U1") (pin "P43") (pinfunction "VCCO_BOTTOM0_P43") (pintype "passive"))
      (node (ref "U1") (pin "P54") (pinfunction "VCCO_BOTTOM1_P54") (pintype "passive"))
      (node (ref "U1") (pin "P66") (pinfunction "VCCO_BOTTOM2_P66") (pintype "passive"))
      (node (ref "U1") (pin "P75") (pinfunction "VCCO_RIGHT0_P75") (pintype "passive"))
      (node (ref "U1") (pin "P91") (pinfunction "VCCO_RIGHT1_P91") (pintype "passive"))
    )
    (net (code "50") (name "/VCC5") (class "Default")
      (node (ref "C33") (pin "+") (pinfunction "+_+") (pintype "passive"))
      (node (ref "C35") (pin "+") (pinfunction "+_+") (pintype "passive"))
      (node (ref "C36") (pin "+") (pinfunction "+_+") (pintype "passive"))
      (node (ref "R5") (pin "2") (pinfunction "2_2") (pintype "passive"))
      (node (ref "R7") (pin "2") (pinfunction "2_2") (pintype "passive"))
      (node (ref "REG1.2") (pin "3") (pinfunction "VCC_3") (pintype "bidirectional"))
      (node (ref "REG2.5") (pin "3") (pinfunction "VCC_3") (pintype "bidirectional"))
      (node (ref "U$4") (pin "3") (pinfunction "VCC_3") (pintype "bidirectional"))
      (node (ref "U$5") (pin "4") (pinfunction "VCC_4") (pintype "bidirectional"))
      (node (ref "X3") (pin "5") (pinfunction "5_5") (pintype "passive"))
      (node (ref "X8") (pin "2") (pinfunction "2_2") (pintype "power_in"))
    )
    (net (code "51") (name "/VCCAUX") (class "Default")
      (node (ref "C18") (pin "1") (pinfunction "1_1") (pintype "passive"))
      (node (ref "C19") (pin "1") (pinfunction "1_1") (pintype "passive"))
      (node (ref "C20") (pin "1") (pinfunction "1_1") (pintype "passive"))
      (node (ref "C21") (pin "1") (pinfunction "1_1") (pintype "passive"))
      (node (ref "R50") (pin "2") (pinfunction "2_2") (pintype "passive"))
      (node (ref "REG2.5") (pin "4") (pinfunction "VOUT1_4") (pintype "bidirectional"))
      (node (ref "U1") (pin "P120") (pinfunction "VCCAUX2_P120") (pintype "passive"))
      (node (ref "U1") (pin "P134") (pinfunction "VCCAUX3_P134") (pintype "passive"))
      (node (ref "U1") (pin "P48") (pinfunction "VCCAUX0_P48") (pintype "passive"))
      (node (ref "U1") (pin "P62") (pinfunction "VCCAUX1_P62") (pintype "passive"))
    )
    (net (code "52") (name "/VCCINT") (class "Default")
      (node (ref "C22") (pin "1") (pinfunction "1_1") (pintype "passive"))
      (node (ref "C23") (pin "1") (pinfunction "1_1") (pintype "passive"))
      (node (ref "C24") (pin "1") (pinfunction "1_1") (pintype "passive"))
      (node (ref "C25") (pin "1") (pinfunction "1_1") (pintype "passive"))
      (node (ref "REG1.2") (pin "4") (pinfunction "VOUT1_4") (pintype "bidirectional"))
      (node (ref "U1") (pin "P121") (pinfunction "VCCINT2_P121") (pintype "passive"))
      (node (ref "U1") (pin "P133") (pinfunction "VCCINT3_P133") (pintype "passive"))
      (node (ref "U1") (pin "P49") (pinfunction "VCCINT0_P49") (pintype "passive"))
      (node (ref "U1") (pin "P61") (pinfunction "VCCINT1_P61") (pintype "passive"))
    )
    (net (code "53") (name "/VCC_B3") (class "Default")
      (node (ref "R11") (pin "2") (pinfunction "2_2") (pintype "passive"))
    )
    (net (code "54") (name "/X6") (class "Default")
      (node (ref "U1") (pin "P51") (pinfunction "IO_L31N_5D4_P51") (pintype "bidirectional"))
    )
    (net (code "57") (name "/XXCSYNC") (class "Default")
      (node (ref "U1") (pin "P137") (pinfunction "IO_L27N_0_P137") (pintype "bidirectional"))
    )
    (net (code "59") (name "GND") (class "Default")
      (node (ref "C1") (pin "1") (pinfunction "1_1") (pintype "passive"))
      (node (ref "C10") (pin "2") (pinfunction "2_2") (pintype "passive"))
      (node (ref "C11") (pin "2") (pinfunction "2_2") (pintype "passive"))
      (node (ref "C12") (pin "2") (pinfunction "2_2") (pintype "passive"))
      (node (ref "C13") (pin "2") (pinfunction "2_2") (pintype "passive"))
      (node (ref "C14") (pin "2") (pinfunction "2_2") (pintype "passive"))
      (node (ref "C15") (pin "2") (pinfunction "2_2") (pintype "passive"))
      (node (ref "C16") (pin "2") (pinfunction "2_2") (pintype "passive"))
      (node (ref "C17") (pin "2") (pinfunction "2_2") (pintype "passive"))
      (node (ref "C18") (pin "2") (pinfunction "2_2") (pintype "passive"))
      (node (ref "C19") (pin "2") (pinfunction "2_2") (pintype "passive"))
      (node (ref "C20") (pin "2") (pinfunction "2_2") (pintype "passive"))
      (node (ref "C21") (pin "2") (pinfunction "2_2") (pintype "passive"))
      (node (ref "C22") (pin "2") (pinfunction "2_2") (pintype "passive"))
      (node (ref "C23") (pin "2") (pinfunction "2_2") (pintype "passive"))
      (node (ref "C24") (pin "2") (pinfunction "2_2") (pintype "passive"))
      (node (ref "C25") (pin "2") (pinfunction "2_2") (pintype "passive"))
      (node (ref "C26") (pin "2") (pinfunction "2_2") (pintype "passive"))
      (node (ref "C27") (pin "2") (pinfunction "2_2") (pintype "passive"))
      (node (ref "C28") (pin "2") (pinfunction "2_2") (pintype "passive"))
      (node (ref "C29") (pin "2") (pinfunction "2_2") (pintype "passive"))
      (node (ref "C30") (pin "2") (pinfunction "2_2") (pintype "passive"))
      (node (ref "C31") (pin "2") (pinfunction "2_2") (pintype "passive"))
      (node (ref "C32") (pin "2") (pinfunction "2_2") (pintype "passive"))
      (node (ref "C33") (pin "-") (pinfunction "-_-") (pintype "passive"))
      (node (ref "C34") (pin "2") (pinfunction "2_2") (pintype "passive"))
      (node (ref "C35") (pin "-") (pinfunction "-_-") (pintype "passive"))
      (node (ref "C36") (pin "-") (pinfunction "-_-") (pintype "passive"))
      (node (ref "C5") (pin "1") (pinfunction "1_1") (pintype "passive"))
      (node (ref "C6") (pin "2") (pinfunction "2_2") (pintype "passive"))
      (node (ref "C7") (pin "2") (pinfunction "2_2") (pintype "passive"))
      (node (ref "C8") (pin "2") (pinfunction "2_2") (pintype "passive"))
      (node (ref "C9") (pin "2") (pinfunction "2_2") (pintype "passive"))
      (node (ref "IC1") (pin "11") (pinfunction "GND_11") (pintype "bidirectional"))
      (node (ref "IC2") (pin "4") (pinfunction "GND_4") (pintype "power_in"))
      (node (ref "IC3") (pin "3") (pinfunction "GND_3") (pintype "bidirectional"))
      (node (ref "JP3") (pin "6") (pinfunction "6_6") (pintype "passive"))
      (node (ref "R12") (pin "1") (pinfunction "1_1") (pintype "passive"))
      (node (ref "R17") (pin "1") (pinfunction "1_1") (pintype "passive"))
      (node (ref "R19") (pin "1") (pinfunction "1_1") (pintype "passive"))
      (node (ref "R21") (pin "1") (pinfunction "1_1") (pintype "passive"))
      (node (ref "REG1.2") (pin "1") (pinfunction "GND_1") (pintype "bidirectional"))
      (node (ref "REG2.5") (pin "1") (pinfunction "GND_1") (pintype "bidirectional"))
      (node (ref "RESET_SW") (pin "2") (pinfunction "2_2") (pintype "passive"))
      (node (ref "U$1") (pin "P24") (pinfunction "VSS_P24") (pintype "bidirectional"))
      (node (ref "U$1") (pin "P30") (pinfunction "CE_P30") (pintype "bidirectional"))
      (node (ref "U$2") (pin "GND") (pinfunction "GND_GND") (pintype "power_in"))
      (node (ref "U$4") (pin "1") (pinfunction "GND_1") (pintype "bidirectional"))
      (node (ref "U$5") (pin "1") (pinfunction "GND_1") (pintype "bidirectional"))
      (node (ref "U$6") (pin "P24") (pinfunction "VSS_P24") (pintype "bidirectional"))
      (node (ref "U$6") (pin "P30") (pinfunction "CE_P30") (pintype "bidirectional"))
      (node (ref "U1") (pin "P101") (pinfunction "GND11_P101") (pintype "passive"))
      (node (ref "U1") (pin "P114") (pinfunction "GND12_P114") (pintype "passive"))
      (node (ref "U1") (pin "P117") (pinfunction "GND13_P117") (pintype "passive"))
      (node (ref "U1") (pin "P136") (pinfunction "GND14_P136") (pintype "passive"))
      (node (ref "U1") (pin "P139") (pinfunction "GND15_P139") (pintype "passive"))
      (node (ref "U1") (pin "P16") (pinfunction "GND1_P16") (pintype "passive"))
      (node (ref "U1") (pin "P22") (pinfunction "GND2_P22") (pintype "passive"))
      (node (ref "U1") (pin "P29") (pinfunction "GND3_P29") (pintype "passive"))
      (node (ref "U1") (pin "P37") (pinfunction "M1_P37") (pintype "bidirectional"))
      (node (ref "U1") (pin "P38") (pinfunction "M0_P38") (pintype "bidirectional"))
      (node (ref "U1") (pin "P39") (pinfunction "M2_P39") (pintype "bidirectional"))
      (node (ref "U1") (pin "P42") (pinfunction "GND4_P42") (pintype "passive"))
      (node (ref "U1") (pin "P45") (pinfunction "GND5_P45") (pintype "passive"))
      (node (ref "U1") (pin "P64") (pinfunction "GND6_P64") (pintype "passive"))
      (node (ref "U1") (pin "P67") (pinfunction "GND7_P67") (pintype "passive"))
      (node (ref "U1") (pin "P81") (pinfunction "GND8_P81") (pintype "passive"))
      (node (ref "U1") (pin "P88") (pinfunction "GND9_P88") (pintype "passive"))
      (node (ref "U1") (pin "P9") (pinfunction "GND0_P9") (pintype "passive"))
      (node (ref "U1") (pin "P94") (pinfunction "GND10_P94") (pintype "passive"))
      (node (ref "X1") (pin "3") (pinfunction "2_3") (pintype "passive"))
      (node (ref "X2") (pin "13") (pinfunction "13_13") (pintype "passive"))
      (node (ref "X2") (pin "14") (pinfunction "14_14") (pintype "passive"))
      (node (ref "X2") (pin "17") (pinfunction "17_17") (pintype "passive"))
      (node (ref "X2") (pin "18") (pinfunction "18_18") (pintype "passive"))
      (node (ref "X2") (pin "21") (pinfunction "21_21") (pintype "passive"))
      (node (ref "X2") (pin "4") (pinfunction "4_4") (pintype "passive"))
      (node (ref "X2") (pin "5") (pinfunction "5_5") (pintype "passive"))
      (node (ref "X2") (pin "9") (pinfunction "9_9") (pintype "passive"))
      (node (ref "X3") (pin "3") (pinfunction "3_3") (pintype "passive"))
      (node (ref "X3") (pin "SH1") (pinfunction "PE1_SH1") (pintype "power_in"))
      (node (ref "X3") (pin "SH2") (pinfunction "PE2_SH2") (pintype "power_in"))
      (node (ref "X3") (pin "SH3") (pinfunction "PE3_SH3") (pintype "power_in"))
      (node (ref "X4") (pin "8") (pinfunction "F_8") (pintype "passive"))
      (node (ref "X4") (pin "G1") (pinfunction "G1_G1") (pintype "passive"))
      (node (ref "X5") (pin "8") (pinfunction "F_8") (pintype "passive"))
      (node (ref "X5") (pin "G1") (pinfunction "G1_G1") (pintype "passive"))
      (node (ref "X8") (pin "1") (pinfunction "1_1") (pintype "power_in"))
      (node (ref "X8") (pin "3") (pinfunction "3_3") (pintype "power_in"))
    )
    (net (code "60") (name "Net-(C1-Pad2)") (class "Default")
      (node (ref "C1") (pin "2") (pinfunction "2_2") (pintype "passive"))
      (node (ref "R23") (pin "2") (pinfunction "2_2") (pintype "passive"))
      (node (ref "R48") (pin "1") (pinfunction "1_1") (pintype "passive"))
    )
    (net (code "61") (name "Net-(C2-Pad1)") (class "Default")
      (node (ref "C2") (pin "1") (pinfunction "1_1") (pintype "passive"))
      (node (ref "R17") (pin "2") (pinfunction "2_2") (pintype "passive"))
      (node (ref "X1") (pin "1") (pinfunction "1_1") (pintype "passive"))
    )
    (net (code "62") (name "Net-(C3-Pad1)") (class "Default")
      (node (ref "C3") (pin "1") (pinfunction "1_1") (pintype "passive"))
      (node (ref "R48") (pin "2") (pinfunction "2_2") (pintype "passive"))
    )
    (net (code "63") (name "Net-(C4-Pad1)") (class "Default")
      (node (ref "C4") (pin "1") (pinfunction "1_1") (pintype "passive"))
      (node (ref "R49") (pin "2") (pinfunction "2_2") (pintype "passive"))
    )
    (net (code "64") (name "Net-(C5-Pad2)") (class "Default")
      (node (ref "C5") (pin "2") (pinfunction "2_2") (pintype "passive"))
      (node (ref "R34") (pin "2") (pinfunction "2_2") (pintype "passive"))
      (node (ref "R49") (pin "1") (pinfunction "1_1") (pintype "passive"))
    )
    (net (code "65") (name "Net-(IC1-CLK)") (class "Default")
      (node (ref "IC1") (pin "3") (pinfunction "CLK_3") (pintype "bidirectional"))
      (node (ref "U1") (pin "P72") (pinfunction "CCLK_P72") (pintype "bidirectional"))
    )
    (net (code "66") (name "Net-(IC1-TDI)") (class "Default")
      (node (ref "IC1") (pin "4") (pinfunction "TDI_4") (pintype "bidirectional"))
      (node (ref "U1") (pin "P109") (pinfunction "TDO_P109") (pintype "bidirectional"))
    )
    (net (code "67") (name "Net-(IC1-{slash}CE)") (class "Default")
      (node (ref "IC1") (pin "10") (pinfunction "/CE_10") (pintype "bidirectional"))
      (node (ref "U1") (pin "P71") (pinfunction "DONE_P71") (pintype "bidirectional"))
    )
    (net (code "68") (name "Net-(IC1-{slash}CF)") (class "Default")
      (node (ref "IC1") (pin "7") (pinfunction "/CF_7") (pintype "bidirectional"))
      (node (ref "U1") (pin "P143") (pinfunction "PROG_B_P143") (pintype "bidirectional"))
    )
    (net (code "69") (name "Net-(IC3-D+)") (class "Default")
      (node (ref "IC3") (pin "29") (pinfunction "D+_29") (pintype "bidirectional"))
      (node (ref "R54") (pin "2") (pinfunction "2_2") (pintype "passive"))
    )
    (net (code "70") (name "Net-(IC3-D-)") (class "Default")
      (node (ref "IC3") (pin "30") (pinfunction "D-_30") (pintype "bidirectional"))
      (node (ref "R53") (pin "2") (pinfunction "2_2") (pintype "passive"))
    )
    (net (code "71") (name "Net-(IC3-UGND)") (class "Default")
      (node (ref "IC3") (pin "28") (pinfunction "UGND_28") (pintype "bidirectional"))
      (node (ref "X6") (pin "4") (pinfunction "4_4") (pintype "passive"))
    )
    (net (code "72") (name "Net-(Q5-B)") (class "Default")
      (node (ref "Q5") (pin "1") (pinfunction "B_1") (pintype "passive"))
      (node (ref "R8") (pin "2") (pinfunction "2_2") (pintype "passive"))
    )
    (net (code "73") (name "Net-(Q5-E)") (class "Default")
      (node (ref "Q5") (pin "2") (pinfunction "E_2") (pintype "passive"))
      (node (ref "R13") (pin "2") (pinfunction "2_2") (pintype "passive"))
      (node (ref "R14") (pin "2") (pinfunction "2_2") (pintype "passive"))
    )
    (net (code "74") (name "Net-(Q6-B)") (class "Default")
      (node (ref "Q6") (pin "1") (pinfunction "B_1") (pintype "passive"))
      (node (ref "R10") (pin "2") (pinfunction "2_2") (pintype "passive"))
      (node (ref "R9") (pin "2") (pinfunction "2_2") (pintype "passive"))
    )
    (net (code "75") (name "Net-(Q6-E)") (class "Default")
      (node (ref "Q6") (pin "2") (pinfunction "E_2") (pintype "passive"))
      (node (ref "R15") (pin "2") (pinfunction "2_2") (pintype "passive"))
      (node (ref "R16") (pin "2") (pinfunction "2_2") (pintype "passive"))
      (node (ref "R20") (pin "2") (pinfunction "2_2") (pintype "passive"))
    )
    (net (code "76") (name "Net-(Q7-B)") (class "Default")
      (node (ref "Q7") (pin "1") (pinfunction "B_1") (pintype "passive"))
      (node (ref "R29") (pin "2") (pinfunction "2_2") (pintype "passive"))
      (node (ref "R30") (pin "2") (pinfunction "2_2") (pintype "passive"))
    )
    (net (code "77") (name "Net-(Q7-E)") (class "Default")
      (node (ref "Q7") (pin "2") (pinfunction "E_2") (pintype "passive"))
      (node (ref "R31") (pin "2") (pinfunction "2_2") (pintype "passive"))
      (node (ref "R32") (pin "2") (pinfunction "2_2") (pintype "passive"))
      (node (ref "R33") (pin "2") (pinfunction "2_2") (pintype "passive"))
    )
    (net (code "78") (name "Net-(Q8-B)") (class "Default")
      (node (ref "Q8") (pin "1") (pinfunction "B_1") (pintype "passive"))
      (node (ref "R24") (pin "2") (pinfunction "2_2") (pintype "passive"))
      (node (ref "R25") (pin "2") (pinfunction "2_2") (pintype "passive"))
    )
    (net (code "79") (name "Net-(Q8-E)") (class "Default")
      (node (ref "Q8") (pin "2") (pinfunction "E_2") (pintype "passive"))
      (node (ref "R26") (pin "2") (pinfunction "2_2") (pintype "passive"))
      (node (ref "R27") (pin "2") (pinfunction "2_2") (pintype "passive"))
      (node (ref "R28") (pin "2") (pinfunction "2_2") (pintype "passive"))
    )
    (net (code "80") (name "Net-(R18-Pad2)") (class "Default")
      (node (ref "R18") (pin "2") (pinfunction "2_2") (pintype "passive"))
      (node (ref "R22") (pin "2") (pinfunction "2_2") (pintype "passive"))
    )
    (net (code "81") (name "Net-(R53-Pad1)") (class "Default")
      (node (ref "R53") (pin "1") (pinfunction "1_1") (pintype "passive"))
      (node (ref "X6") (pin "2") (pinfunction "2_2") (pintype "passive"))
    )
    (net (code "82") (name "Net-(R54-Pad1)") (class "Default")
      (node (ref "R54") (pin "1") (pinfunction "1_1") (pintype "passive"))
      (node (ref "X6") (pin "3") (pinfunction "3_3") (pintype "passive"))
    )
    (net (code "83") (name "Net-(T2-B)") (class "Default")
      (node (ref "C2") (pin "2") (pinfunction "2_2") (pintype "passive"))
      (node (ref "R18") (pin "1") (pinfunction "1_1") (pintype "passive"))
      (node (ref "R19") (pin "2") (pinfunction "2_2") (pintype "passive"))
      (node (ref "T2") (pin "1") (pinfunction "B_1") (pintype "passive"))
    )
    (net (code "84") (name "Net-(U$1-A0)") (class "Default")
      (node (ref "U$1") (pin "P20") (pinfunction "A0_P20") (pintype "bidirectional"))
      (node (ref "U1") (pin "P77") (pinfunction "IO_L20P_3_P77") (pintype "bidirectional"))
    )
    (net (code "85") (name "Net-(U$1-A1)") (class "Default")
      (node (ref "U$1") (pin "P19") (pinfunction "A1_P19") (pintype "bidirectional"))
      (node (ref "U1") (pin "P76") (pinfunction "IO_P76") (pintype "bidirectional"))
    )
    (net (code "86") (name "Net-(U$1-A2)") (class "Default")
      (node (ref "U$1") (pin "P18") (pinfunction "A2_P18") (pintype "bidirectional"))
      (node (ref "U1") (pin "P74") (pinfunction "IO_L01N_3VRP_3_P74") (pintype "bidirectional"))
    )
    (net (code "87") (name "Net-(U$1-A3)") (class "Default")
      (node (ref "U$1") (pin "P17") (pinfunction "A3_P17") (pintype "bidirectional"))
      (node (ref "U1") (pin "P73") (pinfunction "IO_L01P_3VRN_3_P73") (pintype "bidirectional"))
    )
    (net (code "88") (name "Net-(U$1-A4)") (class "Default")
      (node (ref "U$1") (pin "P16") (pinfunction "A4_P16") (pintype "bidirectional"))
      (node (ref "U1") (pin "P108") (pinfunction "IO_L01N_2VRP_2_P108") (pintype "bidirectional"))
    )
    (net (code "89") (name "Net-(U$1-A5)") (class "Default")
      (node (ref "U$1") (pin "P15") (pinfunction "A5_P15") (pintype "bidirectional"))
      (node (ref "U1") (pin "P107") (pinfunction "IO_L01P_2VRN_2_P107") (pintype "bidirectional"))
    )
    (net (code "90") (name "Net-(U$1-A6)") (class "Default")
      (node (ref "U$1") (pin "P14") (pinfunction "A6_P14") (pintype "bidirectional"))
      (node (ref "U1") (pin "P105") (pinfunction "IO_L20N_2_P105") (pintype "bidirectional"))
    )
    (net (code "91") (name "Net-(U$1-A7)") (class "Default")
      (node (ref "U$1") (pin "P13") (pinfunction "A7_P13") (pintype "bidirectional"))
      (node (ref "U1") (pin "P104") (pinfunction "IO_L20P_2_P104") (pintype "bidirectional"))
    )
    (net (code "92") (name "Net-(U$1-A8)") (class "Default")
      (node (ref "U$1") (pin "P3") (pinfunction "A8_P3") (pintype "bidirectional"))
      (node (ref "U1") (pin "P93") (pinfunction "IO_L40N_2_P93") (pintype "bidirectional"))
    )
    (net (code "93") (name "Net-(U$1-A9)") (class "Default")
      (node (ref "U$1") (pin "P2") (pinfunction "A9_P2") (pintype "bidirectional"))
      (node (ref "U1") (pin "P92") (pinfunction "IO_L40P_2VREF_2_P92") (pintype "bidirectional"))
    )
    (net (code "94") (name "Net-(U$1-A10)") (class "Default")
      (node (ref "U$1") (pin "P31") (pinfunction "A10_P31") (pintype "bidirectional"))
      (node (ref "U1") (pin "P87") (pinfunction "IO_L24N_3_P87") (pintype "bidirectional"))
    )
    (net (code "95") (name "Net-(U$1-A11)") (class "Default")
      (node (ref "U$1") (pin "P1") (pinfunction "A11_P1") (pintype "bidirectional"))
      (node (ref "U1") (pin "P90") (pinfunction "IO_L40N_3VREF_3_P90") (pintype "bidirectional"))
    )
    (net (code "96") (name "Net-(U$1-A12)") (class "Default")
      (node (ref "U$1") (pin "P12") (pinfunction "A12_P12") (pintype "bidirectional"))
      (node (ref "U1") (pin "P103") (pinfunction "IO_L21N_2_P103") (pintype "bidirectional"))
    )
    (net (code "97") (name "Net-(U$1-A13)") (class "Default")
      (node (ref "U$1") (pin "P4") (pinfunction "A13_P4") (pintype "bidirectional"))
      (node (ref "U1") (pin "P95") (pinfunction "IO_L24P_2_P95") (pintype "bidirectional"))
    )
    (net (code "98") (name "Net-(U$1-A14)") (class "Default")
      (node (ref "U$1") (pin "P11") (pinfunction "A14_P11") (pintype "bidirectional"))
      (node (ref "U1") (pin "P102") (pinfunction "IO_L21P_2_P102") (pintype "bidirectional"))
    )
    (net (code "99") (name "Net-(U$1-A15)") (class "Default")
      (node (ref "U$1") (pin "P7") (pinfunction "A15_P7") (pintype "bidirectional"))
      (node (ref "U1") (pin "P98") (pinfunction "IO_L23N_2VREF_2_P98") (pintype "bidirectional"))
    )
    (net (code "100") (name "Net-(U$1-A16)") (class "Default")
      (node (ref "U$1") (pin "P10") (pinfunction "A16_P10") (pintype "bidirectional"))
      (node (ref "U1") (pin "P100") (pinfunction "IO_L22N_2_P100") (pintype "bidirectional"))
    )
    (net (code "101") (name "Net-(U$1-A17)") (class "Default")
      (node (ref "U$1") (pin "P6") (pinfunction "A17_P6") (pintype "bidirectional"))
      (node (ref "U1") (pin "P97") (pinfunction "IO_L23P_2_P97") (pintype "bidirectional"))
    )
    (net (code "102") (name "Net-(U$1-A18)") (class "Default")
      (node (ref "U$1") (pin "P9") (pinfunction "A18_P9") (pintype "bidirectional"))
      (node (ref "U1") (pin "P99") (pinfunction "IO_L22P_2_P99") (pintype "bidirectional"))
    )
    (net (code "103") (name "Net-(U$1-DQ0)") (class "Default")
      (node (ref "U$1") (pin "P21") (pinfunction "DQ0_P21") (pintype "bidirectional"))
      (node (ref "U1") (pin "P78") (pinfunction "IO_L20N_3_P78") (pintype "bidirectional"))
    )
    (net (code "104") (name "Net-(U$1-DQ1)") (class "Default")
      (node (ref "U$1") (pin "P22") (pinfunction "DQ1_P22") (pintype "bidirectional"))
      (node (ref "U1") (pin "P79") (pinfunction "IO_L21P_3_P79") (pintype "bidirectional"))
    )
    (net (code "105") (name "Net-(U$1-DQ2)") (class "Default")
      (node (ref "U$1") (pin "P23") (pinfunction "DQ2_P23") (pintype "bidirectional"))
      (node (ref "U1") (pin "P80") (pinfunction "IO_L21N_3_P80") (pintype "bidirectional"))
    )
    (net (code "106") (name "Net-(U$1-DQ3)") (class "Default")
      (node (ref "U$1") (pin "P25") (pinfunction "DQ3_P25") (pintype "bidirectional"))
      (node (ref "U1") (pin "P82") (pinfunction "IO_L22P_3_P82") (pintype "bidirectional"))
    )
    (net (code "107") (name "Net-(U$1-DQ4)") (class "Default")
      (node (ref "U$1") (pin "P26") (pinfunction "DQ4_P26") (pintype "bidirectional"))
      (node (ref "U1") (pin "P83") (pinfunction "IO_L22N_3_P83") (pintype "bidirectional"))
    )
    (net (code "108") (name "Net-(U$1-DQ5)") (class "Default")
      (node (ref "U$1") (pin "P27") (pinfunction "DQ5_P27") (pintype "bidirectional"))
      (node (ref "U1") (pin "P84") (pinfunction "IO_L23P_3VREF_3_P84") (pintype "bidirectional"))
    )
    (net (code "109") (name "Net-(U$1-DQ6)") (class "Default")
      (node (ref "U$1") (pin "P28") (pinfunction "DQ6_P28") (pintype "bidirectional"))
      (node (ref "U1") (pin "P85") (pinfunction "IO_L23N_3_P85") (pintype "bidirectional"))
    )
    (net (code "110") (name "Net-(U$1-DQ7)") (class "Default")
      (node (ref "U$1") (pin "P29") (pinfunction "DQ7_P29") (pintype "bidirectional"))
      (node (ref "U1") (pin "P86") (pinfunction "IO_L24P_3_P86") (pintype "bidirectional"))
    )
    (net (code "111") (name "Net-(U$1-OE)") (class "Default")
      (node (ref "U$1") (pin "P32") (pinfunction "OE_P32") (pintype "bidirectional"))
      (node (ref "U1") (pin "P89") (pinfunction "IO_L40P_3_P89") (pintype "bidirectional"))
    )
    (net (code "112") (name "Net-(U$1-WE)") (class "Default")
      (node (ref "U$1") (pin "P5") (pinfunction "WE_P5") (pintype "bidirectional"))
      (node (ref "U1") (pin "P96") (pinfunction "IO_L24N_2_P96") (pintype "bidirectional"))
    )
    (net (code "113") (name "Net-(U$6-A0)") (class "Default")
      (node (ref "U$6") (pin "P20") (pinfunction "A0_P20") (pintype "bidirectional"))
      (node (ref "U1") (pin "P24") (pinfunction "IO_L24N_6VREF_6_P24") (pintype "bidirectional"))
    )
    (net (code "114") (name "Net-(U$6-A1)") (class "Default")
      (node (ref "U$6") (pin "P19") (pinfunction "A1_P19") (pintype "bidirectional"))
      (node (ref "U1") (pin "P23") (pinfunction "IO_L24P_6_P23") (pintype "bidirectional"))
    )
    (net (code "115") (name "Net-(U$6-A2)") (class "Default")
      (node (ref "U$6") (pin "P18") (pinfunction "A2_P18") (pintype "bidirectional"))
      (node (ref "U1") (pin "P21") (pinfunction "IO_L40N_6_P21") (pintype "bidirectional"))
    )
    (net (code "116") (name "Net-(U$6-A3)") (class "Default")
      (node (ref "U$6") (pin "P17") (pinfunction "A3_P17") (pintype "bidirectional"))
      (node (ref "U1") (pin "P20") (pinfunction "IO_L40P_6VREF_6_P20") (pintype "bidirectional"))
    )
    (net (code "117") (name "Net-(U$6-A4)") (class "Default")
      (node (ref "U$6") (pin "P16") (pinfunction "A4_P16") (pintype "bidirectional"))
      (node (ref "U1") (pin "P18") (pinfunction "IO_L40N_7VREF_7_P18") (pintype "bidirectional"))
    )
    (net (code "118") (name "Net-(U$6-A5)") (class "Default")
      (node (ref "U$6") (pin "P15") (pinfunction "A5_P15") (pintype "bidirectional"))
      (node (ref "U1") (pin "P17") (pinfunction "IO_L40P_7_P17") (pintype "bidirectional"))
    )
    (net (code "119") (name "Net-(U$6-A6)") (class "Default")
      (node (ref "U$6") (pin "P14") (pinfunction "A6_P14") (pintype "bidirectional"))
      (node (ref "U1") (pin "P15") (pinfunction "IO_L24N_7_P15") (pintype "bidirectional"))
    )
    (net (code "120") (name "Net-(U$6-A7)") (class "Default")
      (node (ref "U$6") (pin "P13") (pinfunction "A7_P13") (pintype "bidirectional"))
      (node (ref "U1") (pin "P14") (pinfunction "IO_L24P_7_P14") (pintype "bidirectional"))
    )
    (net (code "121") (name "Net-(U$6-A8)") (class "Default")
      (node (ref "U$6") (pin "P3") (pinfunction "A8_P3") (pintype "bidirectional"))
      (node (ref "U1") (pin "P4") (pinfunction "IOVREF_7_P4") (pintype "bidirectional"))
    )
    (net (code "122") (name "Net-(U$6-A9)") (class "Default")
      (node (ref "U$6") (pin "P2") (pinfunction "A9_P2") (pintype "bidirectional"))
      (node (ref "U1") (pin "P2") (pinfunction "IO_L01N_7VRP_7_P2") (pintype "bidirectional"))
    )
    (net (code "123") (name "Net-(U$6-A10)") (class "Default")
      (node (ref "U$6") (pin "P31") (pinfunction "A10_P31") (pintype "bidirectional"))
      (node (ref "U1") (pin "P35") (pinfunction "IO_L01P_6VRN_6_P35") (pintype "bidirectional"))
    )
    (net (code "124") (name "Net-(U$6-A11)") (class "Default")
      (node (ref "U$6") (pin "P1") (pinfunction "A11_P1") (pintype "bidirectional"))
      (node (ref "U1") (pin "P1") (pinfunction "IO_L01P_7VRN_7_P1") (pintype "bidirectional"))
    )
    (net (code "125") (name "Net-(U$6-A12)") (class "Default")
      (node (ref "U$6") (pin "P12") (pinfunction "A12_P12") (pintype "bidirectional"))
      (node (ref "U1") (pin "P13") (pinfunction "IO_L23N_7_P13") (pintype "bidirectional"))
    )
    (net (code "126") (name "Net-(U$6-A13)") (class "Default")
      (node (ref "U$6") (pin "P4") (pinfunction "A13_P4") (pintype "bidirectional"))
      (node (ref "U1") (pin "P5") (pinfunction "IO_L20P_7_P5") (pintype "bidirectional"))
    )
    (net (code "127") (name "Net-(U$6-A14)") (class "Default")
      (node (ref "U$6") (pin "P11") (pinfunction "A14_P11") (pintype "bidirectional"))
      (node (ref "U1") (pin "P12") (pinfunction "IO_L23P_7_P12") (pintype "bidirectional"))
    )
    (net (code "128") (name "Net-(U$6-A15)") (class "Default")
      (node (ref "U$6") (pin "P7") (pinfunction "A15_P7") (pintype "bidirectional"))
      (node (ref "U1") (pin "P8") (pinfunction "IO_L21N_7_P8") (pintype "bidirectional"))
    )
    (net (code "129") (name "Net-(U$6-A16)") (class "Default")
      (node (ref "U$6") (pin "P10") (pinfunction "A16_P10") (pintype "bidirectional"))
      (node (ref "U1") (pin "P11") (pinfunction "IO_L22N_7_P11") (pintype "bidirectional"))
    )
    (net (code "130") (name "Net-(U$6-A17)") (class "Default")
      (node (ref "U$6") (pin "P6") (pinfunction "A17_P6") (pintype "bidirectional"))
      (node (ref "U1") (pin "P7") (pinfunction "IO_L21P_7_P7") (pintype "bidirectional"))
    )
    (net (code "131") (name "Net-(U$6-A18)") (class "Default")
      (node (ref "U$6") (pin "P9") (pinfunction "A18_P9") (pintype "bidirectional"))
      (node (ref "U1") (pin "P10") (pinfunction "IO_L22P_7_P10") (pintype "bidirectional"))
    )
    (net (code "132") (name "Net-(U$6-DQ0)") (class "Default")
      (node (ref "U$6") (pin "P21") (pinfunction "DQ0_P21") (pintype "bidirectional"))
      (node (ref "U1") (pin "P25") (pinfunction "IO_L23P_6_P25") (pintype "bidirectional"))
    )
    (net (code "133") (name "Net-(U$6-DQ1)") (class "Default")
      (node (ref "U$6") (pin "P22") (pinfunction "DQ1_P22") (pintype "bidirectional"))
      (node (ref "U1") (pin "P26") (pinfunction "IO_L23N_6_P26") (pintype "bidirectional"))
    )
    (net (code "134") (name "Net-(U$6-DQ2)") (class "Default")
      (node (ref "U$6") (pin "P23") (pinfunction "DQ2_P23") (pintype "bidirectional"))
      (node (ref "U1") (pin "P27") (pinfunction "IO_L22P_6_P27") (pintype "bidirectional"))
    )
    (net (code "135") (name "Net-(U$6-DQ3)") (class "Default")
      (node (ref "U$6") (pin "P25") (pinfunction "DQ3_P25") (pintype "bidirectional"))
      (node (ref "U1") (pin "P28") (pinfunction "IO_L22N_6_P28") (pintype "bidirectional"))
    )
    (net (code "136") (name "Net-(U$6-DQ4)") (class "Default")
      (node (ref "U$6") (pin "P26") (pinfunction "DQ4_P26") (pintype "bidirectional"))
      (node (ref "U1") (pin "P30") (pinfunction "IO_L21P_6_P30") (pintype "bidirectional"))
    )
    (net (code "137") (name "Net-(U$6-DQ5)") (class "Default")
      (node (ref "U$6") (pin "P27") (pinfunction "DQ5_P27") (pintype "bidirectional"))
      (node (ref "U1") (pin "P31") (pinfunction "IO_L21N_6_P31") (pintype "bidirectional"))
    )
    (net (code "138") (name "Net-(U$6-DQ6)") (class "Default")
      (node (ref "U$6") (pin "P28") (pinfunction "DQ6_P28") (pintype "bidirectional"))
      (node (ref "U1") (pin "P32") (pinfunction "IO_L20P_6_P32") (pintype "bidirectional"))
    )
    (net (code "139") (name "Net-(U$6-DQ7)") (class "Default")
      (node (ref "U$6") (pin "P29") (pinfunction "DQ7_P29") (pintype "bidirectional"))
      (node (ref "U1") (pin "P33") (pinfunction "IO_L20N_6_P33") (pintype "bidirectional"))
    )
    (net (code "140") (name "Net-(U$6-OE)") (class "Default")
      (node (ref "U$6") (pin "P32") (pinfunction "OE_P32") (pintype "bidirectional"))
      (node (ref "U1") (pin "P36") (pinfunction "IO_L01N_6VRP_6_P36") (pintype "bidirectional"))
    )
    (net (code "141") (name "Net-(U$6-WE)") (class "Default")
      (node (ref "U$6") (pin "P5") (pinfunction "WE_P5") (pintype "bidirectional"))
      (node (ref "U1") (pin "P6") (pinfunction "IO_L20N_7_P6") (pintype "bidirectional"))
    )
    (net (code "142") (name "Net-(U1N-TCK)") (class "Default")
      (node (ref "R2") (pin "1") (pinfunction "1_1") (pintype "passive"))
      (node (ref "U1") (pin "P110") (pinfunction "TCK_P110") (pintype "bidirectional"))
    )
    (net (code "143") (name "Net-(U1N-TDI)") (class "Default")
      (node (ref "R1") (pin "1") (pinfunction "1_1") (pintype "passive"))
      (node (ref "U1") (pin "P144") (pinfunction "TDI_P144") (pintype "bidirectional"))
    )
    (net (code "144") (name "Net-(U1N-TMS)") (class "Default")
      (node (ref "R3") (pin "1") (pinfunction "1_1") (pintype "passive"))
      (node (ref "U1") (pin "P111") (pinfunction "TMS_P111") (pintype "bidirectional"))
    )
    (net (code "145") (name "Net-(X4A-F)") (class "Default")
      (node (ref "R40") (pin "2") (pinfunction "2_2") (pintype "passive"))
      (node (ref "X4") (pin "1") (pinfunction "F_1") (pintype "passive"))
    )
    (net (code "146") (name "Net-(X4B-F)") (class "Default")
      (node (ref "R41") (pin "2") (pinfunction "2_2") (pintype "passive"))
      (node (ref "X4") (pin "2") (pinfunction "F_2") (pintype "passive"))
    )
    (net (code "147") (name "Net-(X4C-F)") (class "Default")
      (node (ref "R42") (pin "2") (pinfunction "2_2") (pintype "passive"))
      (node (ref "X4") (pin "3") (pinfunction "F_3") (pintype "passive"))
    )
    (net (code "148") (name "Net-(X4D-F)") (class "Default")
      (node (ref "R43") (pin "2") (pinfunction "2_2") (pintype "passive"))
      (node (ref "X4") (pin "4") (pinfunction "F_4") (pintype "passive"))
    )
    (net (code "149") (name "Net-(X4F-F)") (class "Default")
      (node (ref "R44") (pin "2") (pinfunction "2_2") (pintype "passive"))
      (node (ref "X4") (pin "6") (pinfunction "F_6") (pintype "passive"))
    )
    (net (code "150") (name "Net-(X4G-F)") (class "Default")
      (node (ref "R45") (pin "2") (pinfunction "2_2") (pintype "passive"))
      (node (ref "X4") (pin "7") (pinfunction "F_7") (pintype "passive"))
    )
    (net (code "151") (name "Net-(X5A-F)") (class "Default")
      (node (ref "R46") (pin "1") (pinfunction "1_1") (pintype "passive"))
      (node (ref "X5") (pin "1") (pinfunction "F_1") (pintype "passive"))
    )
    (net (code "152") (name "Net-(X5B-F)") (class "Default")
      (node (ref "R39") (pin "1") (pinfunction "1_1") (pintype "passive"))
      (node (ref "X5") (pin "2") (pinfunction "F_2") (pintype "passive"))
    )
    (net (code "153") (name "Net-(X5C-F)") (class "Default")
      (node (ref "R38") (pin "1") (pinfunction "1_1") (pintype "passive"))
      (node (ref "X5") (pin "3") (pinfunction "F_3") (pintype "passive"))
    )
    (net (code "154") (name "Net-(X5D-F)") (class "Default")
      (node (ref "R37") (pin "1") (pinfunction "1_1") (pintype "passive"))
      (node (ref "X5") (pin "4") (pinfunction "F_4") (pintype "passive"))
    )
    (net (code "155") (name "Net-(X5F-F)") (class "Default")
      (node (ref "R36") (pin "1") (pinfunction "1_1") (pintype "passive"))
      (node (ref "X5") (pin "6") (pinfunction "F_6") (pintype "passive"))
    )
    (net (code "156") (name "Net-(X5G-F)") (class "Default")
      (node (ref "R35") (pin "1") (pinfunction "1_1") (pintype "passive"))
      (node (ref "X5") (pin "7") (pinfunction "F_7") (pintype "passive"))
    )
    (net (code "157") (name "unconnected-(IC1-NC.1-Pad2)") (class "Default")
      (node (ref "IC1") (pin "2") (pinfunction "NC.1_2") (pintype "bidirectional"))
    )
    (net (code "158") (name "unconnected-(IC1-NC.2-Pad9)") (class "Default")
      (node (ref "IC1") (pin "9") (pinfunction "NC.2_9") (pintype "bidirectional"))
    )
    (net (code "159") (name "unconnected-(IC1-NC.3-Pad12)") (class "Default")
      (node (ref "IC1") (pin "12") (pinfunction "NC.3_12") (pintype "bidirectional"))
    )
    (net (code "160") (name "unconnected-(IC1-NC.4-Pad14)") (class "Default")
      (node (ref "IC1") (pin "14") (pinfunction "NC.4_14") (pintype "bidirectional"))
    )
    (net (code "161") (name "unconnected-(IC1-NC.5-Pad15)") (class "Default")
      (node (ref "IC1") (pin "15") (pinfunction "NC.5_15") (pintype "bidirectional"))
    )
    (net (code "162") (name "unconnected-(IC1-NC.6-Pad16)") (class "Default")
      (node (ref "IC1") (pin "16") (pinfunction "NC.6_16") (pintype "bidirectional"))
    )
    (net (code "163") (name "unconnected-(IC1-{slash}CEO-Pad13)") (class "Default")
      (node (ref "IC1") (pin "13") (pinfunction "/CEO_13") (pintype "bidirectional"))
    )
    (net (code "164") (name "unconnected-(IC3-PC2(AIN2{slash}PCIN11)-Pad5)") (class "Default")
      (node (ref "IC3") (pin "5") (pinfunction "PC2(AIN2/PCIN11)_5") (pintype "bidirectional"))
    )
    (net (code "165") (name "unconnected-(IC3-PC4(PCINT10)-Pad26)") (class "Default")
      (node (ref "IC3") (pin "26") (pinfunction "PC4(PCINT10)_26") (pintype "bidirectional"))
    )
    (net (code "166") (name "unconnected-(IC3-PC5(OC1B{slash}PCINT9)-Pad25)") (class "Default")
      (node (ref "IC3") (pin "25") (pinfunction "PC5(OC1B/PCINT9)_25") (pintype "bidirectional"))
    )
    (net (code "167") (name "unconnected-(IC3-PC6(OC1A{slash}PCINT8)-Pad23)") (class "Default")
      (node (ref "IC3") (pin "23") (pinfunction "PC6(OC1A/PCINT8)_23") (pintype "bidirectional"))
    )
    (net (code "168") (name "unconnected-(IC3-PD0(INT0{slash}OC0B)-Pad6)") (class "Default")
      (node (ref "IC3") (pin "6") (pinfunction "PD0(INT0/OC0B)_6") (pintype "bidirectional"))
    )
    (net (code "169") (name "unconnected-(IC3-PD1(INT1{slash}AIN0)-Pad7)") (class "Default")
      (node (ref "IC3") (pin "7") (pinfunction "PD1(INT1/AIN0)_7") (pintype "bidirectional"))
    )
    (net (code "170") (name "unconnected-(IC3-PD4(INT5{slash}AIN3)-Pad10)") (class "Default")
      (node (ref "IC3") (pin "10") (pinfunction "PD4(INT5/AIN3)_10") (pintype "bidirectional"))
    )
    (net (code "171") (name "unconnected-(IC3-PD5(XCK{slash}AIN4{slash}PCINT12)-Pad11)") (class "Default")
      (node (ref "IC3") (pin "11") (pinfunction "PD5(XCK/AIN4/PCINT12)_11") (pintype "bidirectional"))
    )
    (net (code "172") (name "unconnected-(IC3-PD6(INT6{slash}AIN5{slash}RTS)-Pad12)") (class "Default")
      (node (ref "IC3") (pin "12") (pinfunction "PD6(INT6/AIN5/RTS)_12") (pintype "bidirectional"))
    )
    (net (code "173") (name "unconnected-(IC3-UCAP-Pad27)") (class "Default")
      (node (ref "IC3") (pin "27") (pinfunction "UCAP_27") (pintype "bidirectional"))
    )
    (net (code "174") (name "unconnected-(IC3-XTAL1-Pad1)") (class "Default")
      (node (ref "IC3") (pin "1") (pinfunction "XTAL1_1") (pintype "bidirectional"))
    )
    (net (code "175") (name "unconnected-(IC3-XTAL2{slash}PC0-Pad2)") (class "Default")
      (node (ref "IC3") (pin "2") (pinfunction "XTAL2/PC0_2") (pintype "bidirectional"))
    )
    (net (code "176") (name "unconnected-(IC3-{slash}RESET(PC1)-Pad24)") (class "Default")
      (node (ref "IC3") (pin "24") (pinfunction "/RESET(PC1)_24") (pintype "bidirectional"))
    )
    (net (code "177") (name "unconnected-(JP1-Pad1)") (class "Default")
      (node (ref "JP1") (pin "1") (pinfunction "1_1") (pintype "passive"))
    )
    (net (code "178") (name "unconnected-(JP1-Pad2)") (class "Default")
      (node (ref "JP1") (pin "2") (pinfunction "2_2") (pintype "passive"))
    )
    (net (code "179") (name "unconnected-(JP1-Pad3)") (class "Default")
      (node (ref "JP1") (pin "3") (pinfunction "3_3") (pintype "passive"))
    )
    (net (code "180") (name "unconnected-(JP1-Pad4)") (class "Default")
      (node (ref "JP1") (pin "4") (pinfunction "4_4") (pintype "passive"))
    )
    (net (code "181") (name "unconnected-(JP1-Pad5)") (class "Default")
      (node (ref "JP1") (pin "5") (pinfunction "5_5") (pintype "passive"))
    )
    (net (code "182") (name "unconnected-(JP1-Pad6)") (class "Default")
      (node (ref "JP1") (pin "6") (pinfunction "6_6") (pintype "passive"))
    )
    (net (code "183") (name "unconnected-(JP1-Pad7)") (class "Default")
      (node (ref "JP1") (pin "7") (pinfunction "7_7") (pintype "passive"))
    )
    (net (code "184") (name "unconnected-(JP1-Pad8)") (class "Default")
      (node (ref "JP1") (pin "8") (pinfunction "8_8") (pintype "passive"))
    )
    (net (code "185") (name "unconnected-(JP1-Pad9)") (class "Default")
      (node (ref "JP1") (pin "9") (pinfunction "9_9") (pintype "passive"))
    )
    (net (code "186") (name "unconnected-(JP1-Pad10)") (class "Default")
      (node (ref "JP1") (pin "10") (pinfunction "10_10") (pintype "passive"))
    )
    (net (code "187") (name "unconnected-(JP1-Pad11)") (class "Default")
      (node (ref "JP1") (pin "11") (pinfunction "11_11") (pintype "passive"))
    )
    (net (code "188") (name "unconnected-(JP1-Pad12)") (class "Default")
      (node (ref "JP1") (pin "12") (pinfunction "12_12") (pintype "passive"))
    )
    (net (code "189") (name "unconnected-(JP1-Pad13)") (class "Default")
      (node (ref "JP1") (pin "13") (pinfunction "13_13") (pintype "passive"))
    )
    (net (code "190") (name "unconnected-(JP1-Pad14)") (class "Default")
      (node (ref "JP1") (pin "14") (pinfunction "14_14") (pintype "passive"))
    )
    (net (code "191") (name "unconnected-(JP1-Pad15)") (class "Default")
      (node (ref "JP1") (pin "15") (pinfunction "15_15") (pintype "passive"))
    )
    (net (code "192") (name "unconnected-(JP1-Pad16)") (class "Default")
      (node (ref "JP1") (pin "16") (pinfunction "16_16") (pintype "passive"))
    )
    (net (code "193") (name "unconnected-(JP1-Pad17)") (class "Default")
      (node (ref "JP1") (pin "17") (pinfunction "17_17") (pintype "passive"))
    )
    (net (code "194") (name "unconnected-(JP1-Pad18)") (class "Default")
      (node (ref "JP1") (pin "18") (pinfunction "18_18") (pintype "passive"))
    )
    (net (code "195") (name "unconnected-(JP1-Pad19)") (class "Default")
      (node (ref "JP1") (pin "19") (pinfunction "19_19") (pintype "passive"))
    )
    (net (code "196") (name "unconnected-(JP1-Pad20)") (class "Default")
      (node (ref "JP1") (pin "20") (pinfunction "20_20") (pintype "passive"))
    )
    (net (code "197") (name "unconnected-(JP2-Pad1)") (class "Default")
      (node (ref "JP2") (pin "1") (pinfunction "1_1") (pintype "passive"))
    )
    (net (code "198") (name "unconnected-(JP2-Pad2)") (class "Default")
      (node (ref "JP2") (pin "2") (pinfunction "2_2") (pintype "passive"))
    )
    (net (code "199") (name "unconnected-(JP2-Pad3)") (class "Default")
      (node (ref "JP2") (pin "3") (pinfunction "3_3") (pintype "passive"))
    )
    (net (code "200") (name "unconnected-(JP2-Pad4)") (class "Default")
      (node (ref "JP2") (pin "4") (pinfunction "4_4") (pintype "passive"))
    )
    (net (code "201") (name "unconnected-(JP2-Pad5)") (class "Default")
      (node (ref "JP2") (pin "5") (pinfunction "5_5") (pintype "passive"))
    )
    (net (code "202") (name "unconnected-(JP2-Pad6)") (class "Default")
      (node (ref "JP2") (pin "6") (pinfunction "6_6") (pintype "passive"))
    )
    (net (code "203") (name "unconnected-(JP2-Pad7)") (class "Default")
      (node (ref "JP2") (pin "7") (pinfunction "7_7") (pintype "passive"))
    )
    (net (code "204") (name "unconnected-(JP2-Pad8)") (class "Default")
      (node (ref "JP2") (pin "8") (pinfunction "8_8") (pintype "passive"))
    )
    (net (code "205") (name "unconnected-(JP2-Pad9)") (class "Default")
      (node (ref "JP2") (pin "9") (pinfunction "9_9") (pintype "passive"))
    )
    (net (code "206") (name "unconnected-(JP2-Pad10)") (class "Default")
      (node (ref "JP2") (pin "10") (pinfunction "10_10") (pintype "passive"))
    )
    (net (code "207") (name "unconnected-(JP2-Pad11)") (class "Default")
      (node (ref "JP2") (pin "11") (pinfunction "11_11") (pintype "passive"))
    )
    (net (code "208") (name "unconnected-(JP2-Pad12)") (class "Default")
      (node (ref "JP2") (pin "12") (pinfunction "12_12") (pintype "passive"))
    )
    (net (code "209") (name "unconnected-(JP2-Pad13)") (class "Default")
      (node (ref "JP2") (pin "13") (pinfunction "13_13") (pintype "passive"))
    )
    (net (code "210") (name "unconnected-(JP2-Pad14)") (class "Default")
      (node (ref "JP2") (pin "14") (pinfunction "14_14") (pintype "passive"))
    )
    (net (code "211") (name "unconnected-(JP2-Pad15)") (class "Default")
      (node (ref "JP2") (pin "15") (pinfunction "15_15") (pintype "passive"))
    )
    (net (code "212") (name "unconnected-(JP2-Pad16)") (class "Default")
      (node (ref "JP2") (pin "16") (pinfunction "16_16") (pintype "passive"))
    )
    (net (code "213") (name "unconnected-(JP2-Pad17)") (class "Default")
      (node (ref "JP2") (pin "17") (pinfunction "17_17") (pintype "passive"))
    )
    (net (code "214") (name "unconnected-(JP2-Pad18)") (class "Default")
      (node (ref "JP2") (pin "18") (pinfunction "18_18") (pintype "passive"))
    )
    (net (code "215") (name "unconnected-(JP2-Pad19)") (class "Default")
      (node (ref "JP2") (pin "19") (pinfunction "19_19") (pintype "passive"))
    )
    (net (code "216") (name "unconnected-(JP2-Pad20)") (class "Default")
      (node (ref "JP2") (pin "20") (pinfunction "20_20") (pintype "passive"))
    )
    (net (code "217") (name "unconnected-(REG1.2-VOUT2-Pad2)") (class "Default")
      (node (ref "REG1.2") (pin "2") (pinfunction "VOUT2_2") (pintype "bidirectional"))
    )
    (net (code "218") (name "unconnected-(REG2.5-VOUT2-Pad2)") (class "Default")
      (node (ref "REG2.5") (pin "2") (pinfunction "VOUT2_2") (pintype "bidirectional"))
    )
    (net (code "219") (name "unconnected-(U$2-TRI-PadENA)") (class "Default")
      (node (ref "U$2") (pin "ENA") (pinfunction "TRI_ENA") (pintype "input"))
    )
    (net (code "220") (name "unconnected-(U$4-VOUT2-Pad2)") (class "Default")
      (node (ref "U$4") (pin "2") (pinfunction "VOUT2_2") (pintype "bidirectional"))
    )
    (net (code "221") (name "unconnected-(U1A-IO_L27P_0-PadP135)") (class "Default")
      (node (ref "U1") (pin "P135") (pinfunction "IO_L27P_0_P135") (pintype "bidirectional"))
    )
    (net (code "222") (name "unconnected-(U1A-IO_L30N_0-PadP132)") (class "Default")
      (node (ref "U1") (pin "P132") (pinfunction "IO_L30N_0_P132") (pintype "bidirectional"))
    )
    (net (code "223") (name "unconnected-(U1A-IO_L30P_0-PadP131)") (class "Default")
      (node (ref "U1") (pin "P131") (pinfunction "IO_L30P_0_P131") (pintype "bidirectional"))
    )
    (net (code "224") (name "unconnected-(U1A-IO_L31N_0-PadP130)") (class "Default")
      (node (ref "U1") (pin "P130") (pinfunction "IO_L31N_0_P130") (pintype "bidirectional"))
    )
    (net (code "225") (name "unconnected-(U1A-IO_L31P_0VREF_0-PadP129)") (class "Default")
      (node (ref "U1") (pin "P129") (pinfunction "IO_L31P_0VREF_0_P129") (pintype "bidirectional"))
    )
    (net (code "226") (name "unconnected-(U1A-IO_L32N_0GCLK7-PadP128)") (class "Default")
      (node (ref "U1") (pin "P128") (pinfunction "IO_L32N_0GCLK7_P128") (pintype "bidirectional"))
    )
    (net (code "227") (name "unconnected-(U1A-IO_L32P_0GCLK6-PadP127)") (class "Default")
      (node (ref "U1") (pin "P127") (pinfunction "IO_L32P_0GCLK6_P127") (pintype "bidirectional"))
    )
    (net (code "228") (name "unconnected-(U1C-IO-PadP116)") (class "Default")
      (node (ref "U1") (pin "P116") (pinfunction "IO_P116") (pintype "bidirectional"))
    )
    (net (code "229") (name "unconnected-(U1C-IO_L01N_1VRP_1-PadP113)") (class "Default")
      (node (ref "U1") (pin "P113") (pinfunction "IO_L01N_1VRP_1_P113") (pintype "bidirectional"))
    )
    (net (code "230") (name "unconnected-(U1C-IO_L01P_1VRN_1-PadP112)") (class "Default")
      (node (ref "U1") (pin "P112") (pinfunction "IO_L01P_1VRN_1_P112") (pintype "bidirectional"))
    )
    (net (code "231") (name "unconnected-(U1C-IO_L28N_1-PadP119)") (class "Default")
      (node (ref "U1") (pin "P119") (pinfunction "IO_L28N_1_P119") (pintype "bidirectional"))
    )
    (net (code "232") (name "unconnected-(U1C-IO_L28P_1-PadP118)") (class "Default")
      (node (ref "U1") (pin "P118") (pinfunction "IO_L28P_1_P118") (pintype "bidirectional"))
    )
    (net (code "233") (name "unconnected-(U1C-IO_L31N_1VREF_1-PadP123)") (class "Default")
      (node (ref "U1") (pin "P123") (pinfunction "IO_L31N_1VREF_1_P123") (pintype "bidirectional"))
    )
    (net (code "234") (name "unconnected-(U1C-IO_L31P_1-PadP122)") (class "Default")
      (node (ref "U1") (pin "P122") (pinfunction "IO_L31P_1_P122") (pintype "bidirectional"))
    )
    (net (code "235") (name "unconnected-(U1C-IO_L32N_1GCLK5-PadP125)") (class "Default")
      (node (ref "U1") (pin "P125") (pinfunction "IO_L32N_1GCLK5_P125") (pintype "bidirectional"))
    )
    (net (code "236") (name "unconnected-(U1C-IO_L32P_1GCLK4-PadP124)") (class "Default")
      (node (ref "U1") (pin "P124") (pinfunction "IO_L32P_1GCLK4_P124") (pintype "bidirectional"))
    )
    (net (code "237") (name "unconnected-(U1N-HSWAP_EN-PadP142)") (class "Default")
      (node (ref "U1") (pin "P142") (pinfunction "HSWAP_EN_P142") (pintype "bidirectional"))
    )
    (net (code "238") (name "unconnected-(X1-3-Pad2)") (class "Default")
      (node (ref "X1") (pin "2") (pinfunction "3_2") (pintype "passive"))
    )
    (net (code "239") (name "unconnected-(X2-Pad10)") (class "Default")
      (node (ref "X2") (pin "10") (pinfunction "10_10") (pintype "passive"))
    )
    (net (code "240") (name "unconnected-(X2-Pad12)") (class "Default")
      (node (ref "X2") (pin "12") (pinfunction "12_12") (pintype "passive"))
    )
    (net (code "241") (name "unconnected-(X3-Pad2)") (class "Default")
      (node (ref "X3") (pin "2") (pinfunction "2_2") (pintype "passive"))
    )
    (net (code "242") (name "unconnected-(X3-Pad8)") (class "Default")
      (node (ref "X3") (pin "8") (pinfunction "8_8") (pintype "passive"))
    )
    (net (code "243") (name "unconnected-(X4-PadG2)") (class "Default")
      (node (ref "X4") (pin "G2") (pinfunction "G2_G2") (pintype "passive"))
    )
    (net (code "244") (name "unconnected-(X5-PadG2)") (class "Default")
      (node (ref "X5") (pin "G2") (pinfunction "G2_G2") (pintype "passive"))
    )
    (net (code "245") (name "unconnected-(X6-Pad1)") (class "Default")
      (node (ref "X6") (pin "1") (pinfunction "1_1") (pintype "passive"))
    )
  )
)
